# Processing_Unit.net
KiCad netlist of a schematic drawn in Altium Designer
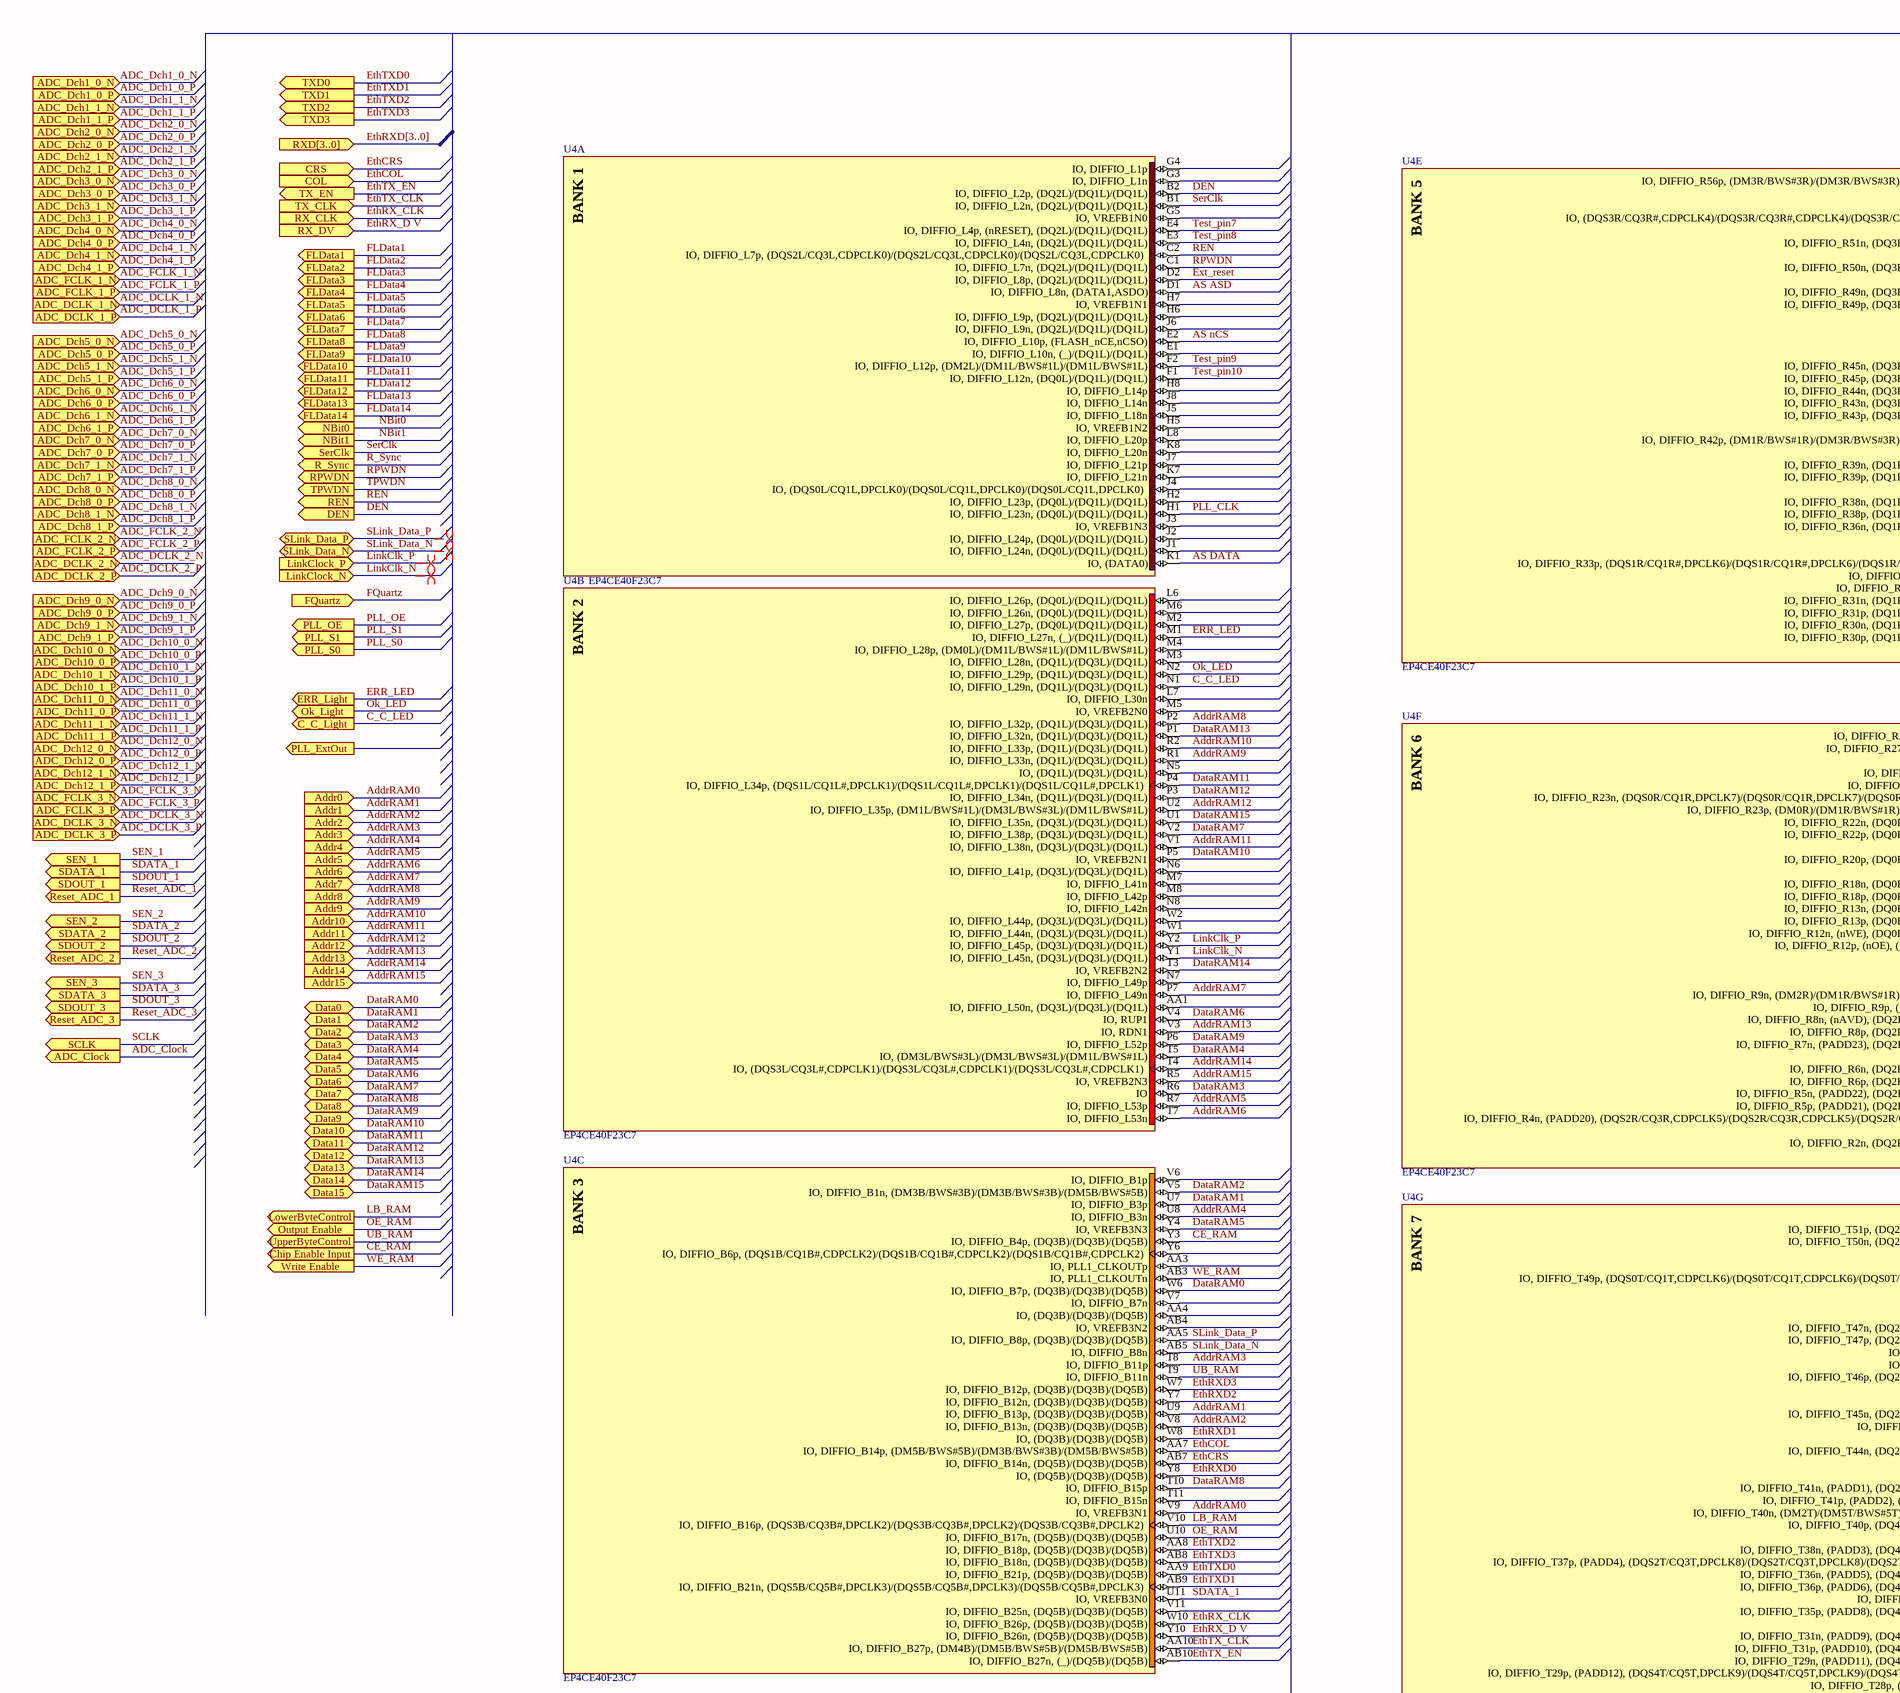
[diagram p0: Processing Unit.SchDoc, top left]
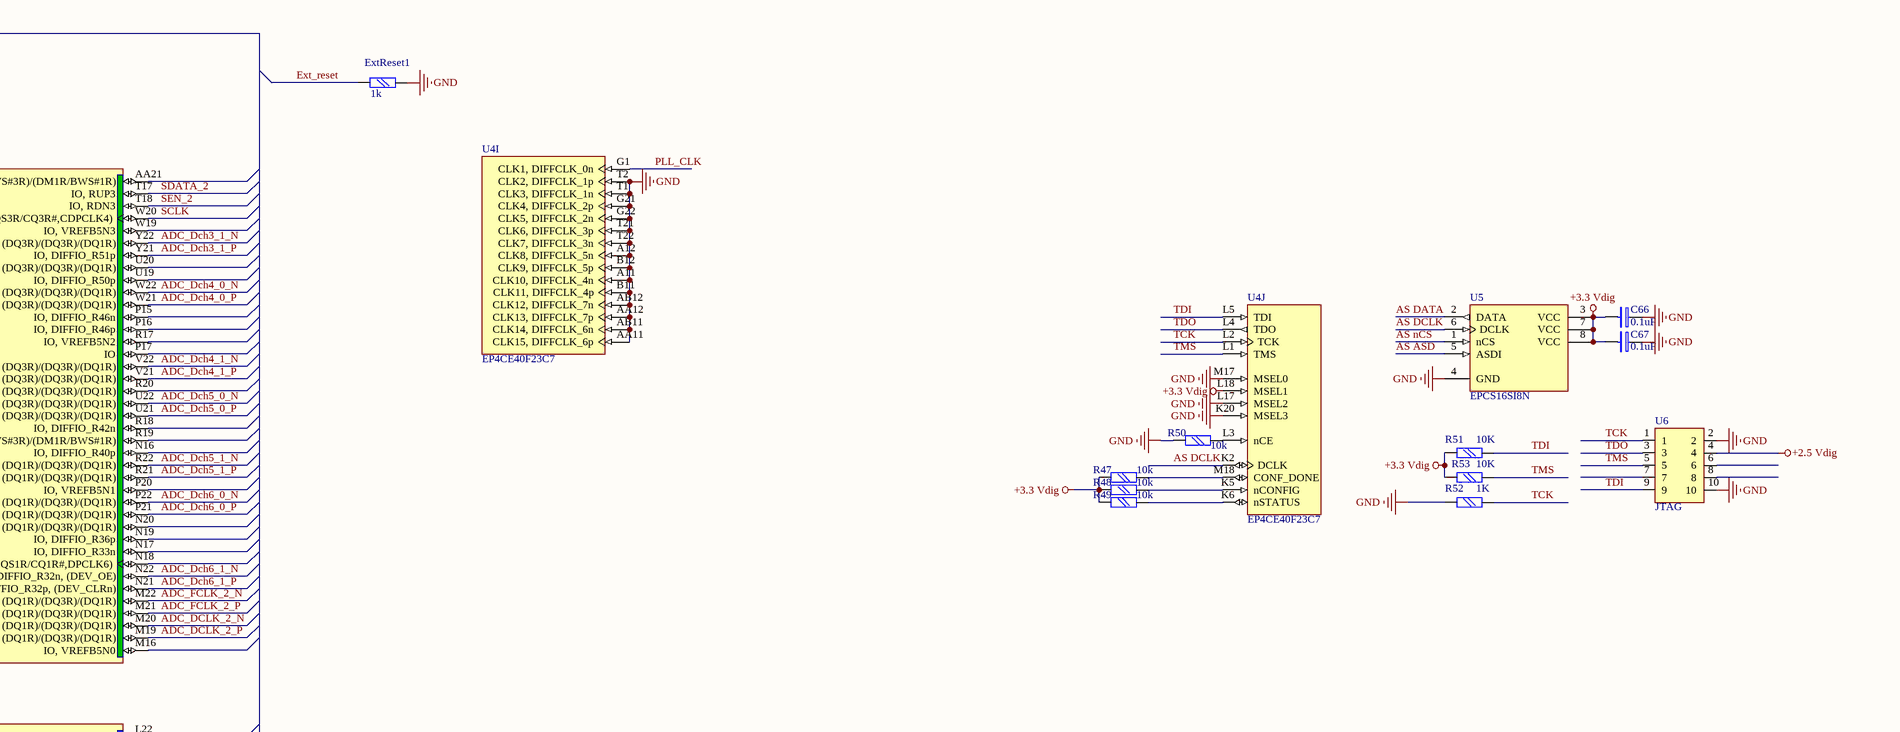
[diagram p1: Processing Unit.SchDoc, top right]
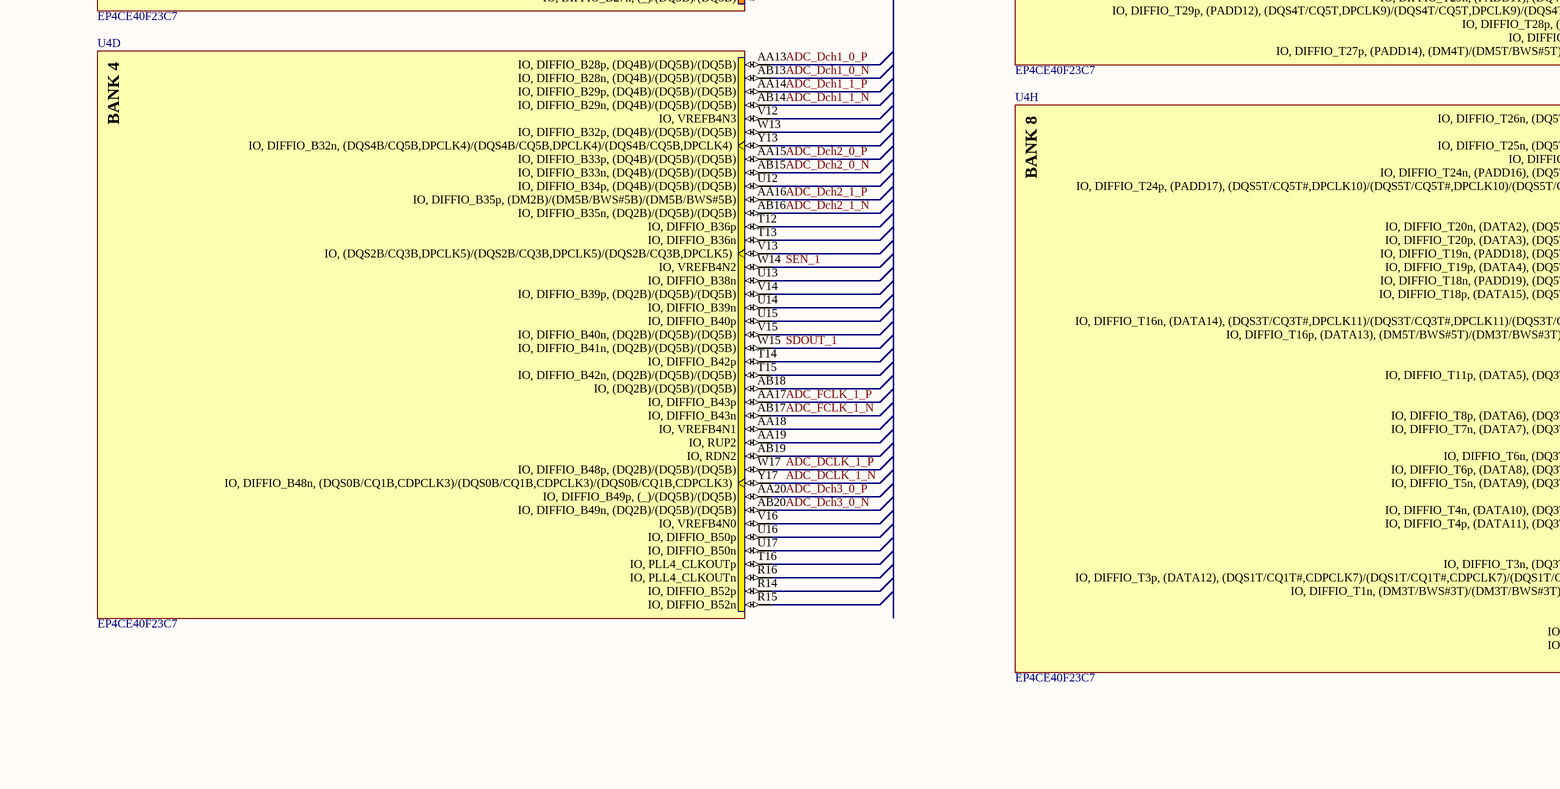
[diagram p2: Processing Unit.SchDoc, bottom left]
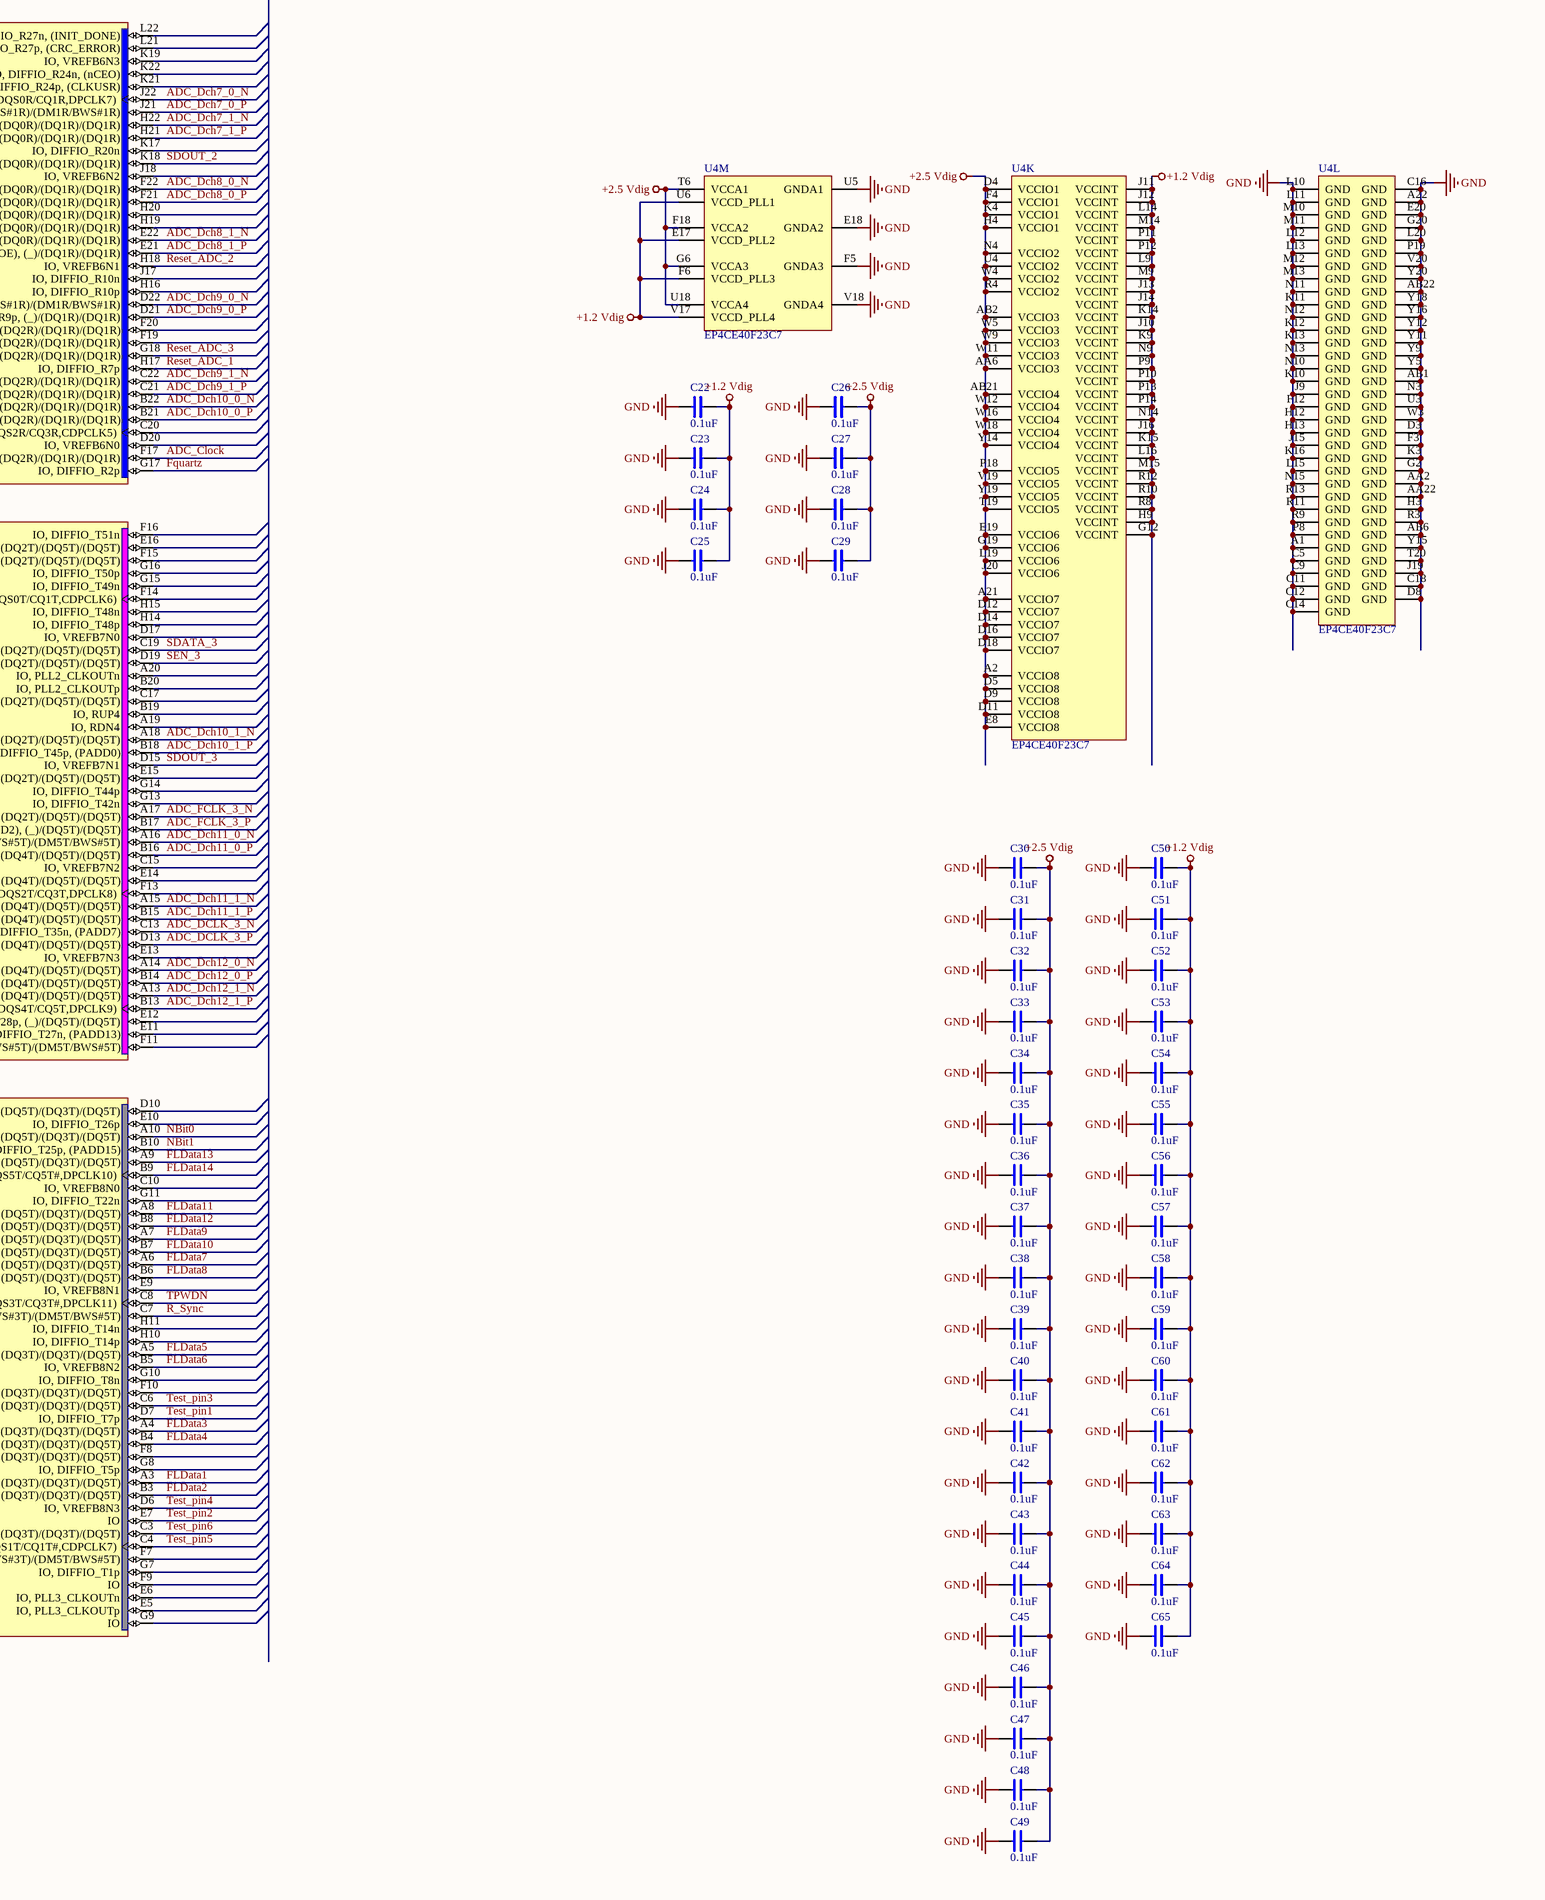
[diagram p3: Processing Unit.SchDoc, bottom right]

(export (version "E")
  (design (tool "Eeschema 10.0.6"))
  (components
    (comp (ref "C22") (value "0.1uF") (footprint "0402") (libsource (lib "*") (part "C")))
    (comp (ref "C23") (value "0.1uF") (footprint "0402") (libsource (lib "*") (part "C")))
    (comp (ref "C24") (value "0.1uF") (footprint "0402") (libsource (lib "*") (part "C")))
    (comp (ref "C25") (value "0.1uF") (footprint "0402") (libsource (lib "*") (part "C")))
    (comp (ref "C26") (value "0.1uF") (footprint "0402") (libsource (lib "*") (part "C")))
    (comp (ref "C27") (value "0.1uF") (footprint "0402") (libsource (lib "*") (part "C")))
    (comp (ref "C28") (value "0.1uF") (footprint "0402") (libsource (lib "*") (part "C")))
    (comp (ref "C29") (value "0.1uF") (footprint "0402") (libsource (lib "*") (part "C")))
    (comp (ref "C30") (value "0.1uF") (footprint "0402") (libsource (lib "*") (part "C")))
    (comp (ref "C31") (value "0.1uF") (footprint "0402") (libsource (lib "*") (part "C")))
    (comp (ref "C32") (value "0.1uF") (footprint "0402") (libsource (lib "*") (part "C")))
    (comp (ref "C33") (value "0.1uF") (footprint "0402") (libsource (lib "*") (part "C")))
    (comp (ref "C34") (value "0.1uF") (footprint "0402") (libsource (lib "*") (part "C")))
    (comp (ref "C35") (value "0.1uF") (footprint "0402") (libsource (lib "*") (part "C")))
    (comp (ref "C36") (value "0.1uF") (footprint "0402") (libsource (lib "*") (part "C")))
    (comp (ref "C37") (value "0.1uF") (footprint "0402") (libsource (lib "*") (part "C")))
    (comp (ref "C38") (value "0.1uF") (footprint "0402") (libsource (lib "*") (part "C")))
    (comp (ref "C39") (value "0.1uF") (footprint "0402") (libsource (lib "*") (part "C")))
    (comp (ref "C40") (value "0.1uF") (footprint "0402") (libsource (lib "*") (part "C")))
    (comp (ref "C41") (value "0.1uF") (footprint "0402") (libsource (lib "*") (part "C")))
    (comp (ref "C42") (value "0.1uF") (footprint "0402") (libsource (lib "*") (part "C")))
    (comp (ref "C43") (value "0.1uF") (footprint "0402") (libsource (lib "*") (part "C")))
    (comp (ref "C44") (value "0.1uF") (footprint "0402") (libsource (lib "*") (part "C")))
    (comp (ref "C45") (value "0.1uF") (footprint "0402") (libsource (lib "*") (part "C")))
    (comp (ref "C46") (value "0.1uF") (footprint "0402") (libsource (lib "*") (part "C")))
    (comp (ref "C47") (value "0.1uF") (footprint "0402") (libsource (lib "*") (part "C")))
    (comp (ref "C48") (value "0.1uF") (footprint "0402") (libsource (lib "*") (part "C")))
    (comp (ref "C49") (value "0.1uF") (footprint "0402") (libsource (lib "*") (part "C")))
    (comp (ref "C50") (value "0.1uF") (footprint "0402") (libsource (lib "*") (part "C")))
    (comp (ref "C51") (value "0.1uF") (footprint "0402") (libsource (lib "*") (part "C")))
    (comp (ref "C52") (value "0.1uF") (footprint "0402") (libsource (lib "*") (part "C")))
    (comp (ref "C53") (value "0.1uF") (footprint "0402") (libsource (lib "*") (part "C")))
    (comp (ref "C54") (value "0.1uF") (footprint "0402") (libsource (lib "*") (part "C")))
    (comp (ref "C55") (value "0.1uF") (footprint "0402") (libsource (lib "*") (part "C")))
    (comp (ref "C56") (value "0.1uF") (footprint "0402") (libsource (lib "*") (part "C")))
    (comp (ref "C57") (value "0.1uF") (footprint "0402") (libsource (lib "*") (part "C")))
    (comp (ref "C58") (value "0.1uF") (footprint "0402") (libsource (lib "*") (part "C")))
    (comp (ref "C59") (value "0.1uF") (footprint "0402") (libsource (lib "*") (part "C")))
    (comp (ref "C60") (value "0.1uF") (footprint "0402") (libsource (lib "*") (part "C")))
    (comp (ref "C61") (value "0.1uF") (footprint "0402") (libsource (lib "*") (part "C")))
    (comp (ref "C62") (value "0.1uF") (footprint "0402") (libsource (lib "*") (part "C")))
    (comp (ref "C63") (value "0.1uF") (footprint "0402") (libsource (lib "*") (part "C")))
    (comp (ref "C64") (value "0.1uF") (footprint "0402") (libsource (lib "*") (part "C")))
    (comp (ref "C65") (value "0.1uF") (footprint "0402") (libsource (lib "*") (part "C")))
    (comp (ref "C66") (value "0.1uF") (footprint "chip0603") (libsource (lib "*") (part "C")))
    (comp (ref "C67") (value "0.1uF") (footprint "chip0603") (libsource (lib "*") (part "C")))
    (comp (ref "ExtReset1") (value "1k") (footprint "chip0603") (libsource (lib "*") (part "R")))
    (comp (ref "R47") (value "10k") (footprint "chip0603") (libsource (lib "") (part "R_1")))
    (comp (ref "R48") (value "10k") (footprint "chip0603") (libsource (lib "") (part "R_1")))
    (comp (ref "R49") (value "10k") (footprint "chip0603") (libsource (lib "") (part "R_1")))
    (comp (ref "R50") (value "10k") (footprint "chip0603") (libsource (lib "") (part "R_1")))
    (comp (ref "R51") (value "10K") (footprint "chip0603") (libsource (lib "") (part "R_1")))
    (comp (ref "R52") (value "1K") (footprint "chip0603") (libsource (lib "") (part "R_1")))
    (comp (ref "R53") (value "10K") (footprint "chip0603") (libsource (lib "") (part "R_1")))
    (comp (ref "U4")
      (value "EP4CE40F23C7")
      (footprint "Altera Footprints:FBGA484")
      (fields (field (name "PUBLISHER") "Altium Limited"))
      (libsource (lib "Altera Cyclone IV E") (part "EP4CE40F23C7"))
    )
    (comp (ref "U5")
      (value "EPCS16SI8N")
      (footprint "8SO200")
      (fields (field (name "PUBLISHER") "Altium Limited"))
      (libsource (lib "Altera EPCS Configuration Device") (part "EPCS4SI8N"))
    )
    (comp (ref "U6") (value "JTAG") (footprint "IDC10") (libsource (lib "vDevice") (part "IDC-10")))
  )
  (nets
    (net (code "1") (name "+1.2 Vdig") (class "Default")
      (node (ref "C22") (pin "2") (pinfunction "2_2") (pintype "passive"))
      (node (ref "C23") (pin "2") (pinfunction "2_2") (pintype "passive"))
      (node (ref "C24") (pin "2") (pinfunction "2_2") (pintype "passive"))
      (node (ref "C25") (pin "2") (pinfunction "2_2") (pintype "passive"))
      (node (ref "C50") (pin "2") (pinfunction "2_2") (pintype "passive"))
      (node (ref "C51") (pin "2") (pinfunction "2_2") (pintype "passive"))
      (node (ref "C52") (pin "2") (pinfunction "2_2") (pintype "passive"))
      (node (ref "C53") (pin "2") (pinfunction "2_2") (pintype "passive"))
      (node (ref "C54") (pin "2") (pinfunction "2_2") (pintype "passive"))
      (node (ref "C55") (pin "2") (pinfunction "2_2") (pintype "passive"))
      (node (ref "C56") (pin "2") (pinfunction "2_2") (pintype "passive"))
      (node (ref "C57") (pin "2") (pinfunction "2_2") (pintype "passive"))
      (node (ref "C58") (pin "2") (pinfunction "2_2") (pintype "passive"))
      (node (ref "C59") (pin "2") (pinfunction "2_2") (pintype "passive"))
      (node (ref "C60") (pin "2") (pinfunction "2_2") (pintype "passive"))
      (node (ref "C61") (pin "2") (pinfunction "2_2") (pintype "passive"))
      (node (ref "C62") (pin "2") (pinfunction "2_2") (pintype "passive"))
      (node (ref "C63") (pin "2") (pinfunction "2_2") (pintype "passive"))
      (node (ref "C64") (pin "2") (pinfunction "2_2") (pintype "passive"))
      (node (ref "C65") (pin "2") (pinfunction "2_2") (pintype "passive"))
      (node (ref "U4") (pin "E17") (pinfunction "VCCD_PLL2_E17") (pintype "power_in"))
      (node (ref "U4") (pin "F6") (pinfunction "VCCD_PLL3_F6") (pintype "power_in"))
      (node (ref "U4") (pin "G12") (pinfunction "VCCINT_G12") (pintype "power_in"))
      (node (ref "U4") (pin "H9") (pinfunction "VCCINT_H9") (pintype "power_in"))
      (node (ref "U4") (pin "J10") (pinfunction "VCCINT_J10") (pintype "power_in"))
      (node (ref "U4") (pin "J11") (pinfunction "VCCINT_J11") (pintype "power_in"))
      (node (ref "U4") (pin "J12") (pinfunction "VCCINT_J12") (pintype "power_in"))
      (node (ref "U4") (pin "J13") (pinfunction "VCCINT_J13") (pintype "power_in"))
      (node (ref "U4") (pin "J14") (pinfunction "VCCINT_J14") (pintype "power_in"))
      (node (ref "U4") (pin "J16") (pinfunction "VCCINT_J16") (pintype "power_in"))
      (node (ref "U4") (pin "K14") (pinfunction "VCCINT_K14") (pintype "power_in"))
      (node (ref "U4") (pin "K15") (pinfunction "VCCINT_K15") (pintype "power_in"))
      (node (ref "U4") (pin "K9") (pinfunction "VCCINT_K9") (pintype "power_in"))
      (node (ref "U4") (pin "L14") (pinfunction "VCCINT_L14") (pintype "power_in"))
      (node (ref "U4") (pin "L16") (pinfunction "VCCINT_L16") (pintype "power_in"))
      (node (ref "U4") (pin "L9") (pinfunction "VCCINT_L9") (pintype "power_in"))
      (node (ref "U4") (pin "M14") (pinfunction "VCCINT_M14") (pintype "power_in"))
      (node (ref "U4") (pin "M15") (pinfunction "VCCINT_M15") (pintype "power_in"))
      (node (ref "U4") (pin "M9") (pinfunction "VCCINT_M9") (pintype "power_in"))
      (node (ref "U4") (pin "N14") (pinfunction "VCCINT_N14") (pintype "power_in"))
      (node (ref "U4") (pin "N9") (pinfunction "VCCINT_N9") (pintype "power_in"))
      (node (ref "U4") (pin "P10") (pinfunction "VCCINT_P10") (pintype "power_in"))
      (node (ref "U4") (pin "P11") (pinfunction "VCCINT_P11") (pintype "power_in"))
      (node (ref "U4") (pin "P12") (pinfunction "VCCINT_P12") (pintype "power_in"))
      (node (ref "U4") (pin "P13") (pinfunction "VCCINT_P13") (pintype "power_in"))
      (node (ref "U4") (pin "P14") (pinfunction "VCCINT_P14") (pintype "power_in"))
      (node (ref "U4") (pin "P9") (pinfunction "VCCINT_P9") (pintype "power_in"))
      (node (ref "U4") (pin "R10") (pinfunction "VCCINT_R10") (pintype "power_in"))
      (node (ref "U4") (pin "R12") (pinfunction "VCCINT_R12") (pintype "power_in"))
      (node (ref "U4") (pin "R8") (pinfunction "VCCINT_R8") (pintype "power_in"))
      (node (ref "U4") (pin "U6") (pinfunction "VCCD_PLL1_U6") (pintype "power_in"))
      (node (ref "U4") (pin "V17") (pinfunction "VCCD_PLL4_V17") (pintype "power_in"))
    )
    (net (code "2") (name "+2.5 Vdig") (class "Default")
      (node (ref "C26") (pin "2") (pinfunction "2_2") (pintype "passive"))
      (node (ref "C27") (pin "2") (pinfunction "2_2") (pintype "passive"))
      (node (ref "C28") (pin "2") (pinfunction "2_2") (pintype "passive"))
      (node (ref "C29") (pin "2") (pinfunction "2_2") (pintype "passive"))
      (node (ref "C30") (pin "2") (pinfunction "2_2") (pintype "passive"))
      (node (ref "C31") (pin "2") (pinfunction "2_2") (pintype "passive"))
      (node (ref "C32") (pin "2") (pinfunction "2_2") (pintype "passive"))
      (node (ref "C33") (pin "2") (pinfunction "2_2") (pintype "passive"))
      (node (ref "C34") (pin "2") (pinfunction "2_2") (pintype "passive"))
      (node (ref "C35") (pin "2") (pinfunction "2_2") (pintype "passive"))
      (node (ref "C36") (pin "2") (pinfunction "2_2") (pintype "passive"))
      (node (ref "C37") (pin "2") (pinfunction "2_2") (pintype "passive"))
      (node (ref "C38") (pin "2") (pinfunction "2_2") (pintype "passive"))
      (node (ref "C39") (pin "2") (pinfunction "2_2") (pintype "passive"))
      (node (ref "C40") (pin "2") (pinfunction "2_2") (pintype "passive"))
      (node (ref "C41") (pin "2") (pinfunction "2_2") (pintype "passive"))
      (node (ref "C42") (pin "2") (pinfunction "2_2") (pintype "passive"))
      (node (ref "C43") (pin "2") (pinfunction "2_2") (pintype "passive"))
      (node (ref "C44") (pin "2") (pinfunction "2_2") (pintype "passive"))
      (node (ref "C45") (pin "2") (pinfunction "2_2") (pintype "passive"))
      (node (ref "C46") (pin "2") (pinfunction "2_2") (pintype "passive"))
      (node (ref "C47") (pin "2") (pinfunction "2_2") (pintype "passive"))
      (node (ref "C48") (pin "2") (pinfunction "2_2") (pintype "passive"))
      (node (ref "C49") (pin "2") (pinfunction "2_2") (pintype "passive"))
      (node (ref "U4") (pin "A2") (pinfunction "VCCIO8_A2") (pintype "power_in"))
      (node (ref "U4") (pin "A21") (pinfunction "VCCIO7_A21") (pintype "power_in"))
      (node (ref "U4") (pin "AA6") (pinfunction "VCCIO3_AA6") (pintype "power_in"))
      (node (ref "U4") (pin "AB2") (pinfunction "VCCIO3_AB2") (pintype "power_in"))
      (node (ref "U4") (pin "AB21") (pinfunction "VCCIO4_AB21") (pintype "power_in"))
      (node (ref "U4") (pin "D11") (pinfunction "VCCIO8_D11") (pintype "power_in"))
      (node (ref "U4") (pin "D12") (pinfunction "VCCIO7_D12") (pintype "power_in"))
      (node (ref "U4") (pin "D14") (pinfunction "VCCIO7_D14") (pintype "power_in"))
      (node (ref "U4") (pin "D16") (pinfunction "VCCIO7_D16") (pintype "power_in"))
      (node (ref "U4") (pin "D18") (pinfunction "VCCIO7_D18") (pintype "power_in"))
      (node (ref "U4") (pin "D4") (pinfunction "VCCIO1_D4") (pintype "power_in"))
      (node (ref "U4") (pin "D5") (pinfunction "VCCIO8_D5") (pintype "power_in"))
      (node (ref "U4") (pin "D9") (pinfunction "VCCIO8_D9") (pintype "power_in"))
      (node (ref "U4") (pin "E19") (pinfunction "VCCIO6_E19") (pintype "power_in"))
      (node (ref "U4") (pin "E8") (pinfunction "VCCIO8_E8") (pintype "power_in"))
      (node (ref "U4") (pin "F18") (pinfunction "VCCA2_F18") (pintype "power_in"))
      (node (ref "U4") (pin "F4") (pinfunction "VCCIO1_F4") (pintype "power_in"))
      (node (ref "U4") (pin "G19") (pinfunction "VCCIO6_G19") (pintype "power_in"))
      (node (ref "U4") (pin "G6") (pinfunction "VCCA3_G6") (pintype "power_in"))
      (node (ref "U4") (pin "H4") (pinfunction "VCCIO1_H4") (pintype "power_in"))
      (node (ref "U4") (pin "J20") (pinfunction "VCCIO6_J20") (pintype "power_in"))
      (node (ref "U4") (pin "K4") (pinfunction "VCCIO1_K4") (pintype "power_in"))
      (node (ref "U4") (pin "L19") (pinfunction "VCCIO6_L19") (pintype "power_in"))
      (node (ref "U4") (pin "N4") (pinfunction "VCCIO2_N4") (pintype "power_in"))
      (node (ref "U4") (pin "P18") (pinfunction "VCCIO5_P18") (pintype "power_in"))
      (node (ref "U4") (pin "R4") (pinfunction "VCCIO2_R4") (pintype "power_in"))
      (node (ref "U4") (pin "T19") (pinfunction "VCCIO5_T19") (pintype "power_in"))
      (node (ref "U4") (pin "T6") (pinfunction "VCCA1_T6") (pintype "power_in"))
      (node (ref "U4") (pin "U18") (pinfunction "VCCA4_U18") (pintype "power_in"))
      (node (ref "U4") (pin "U4") (pinfunction "VCCIO2_U4") (pintype "power_in"))
      (node (ref "U4") (pin "V19") (pinfunction "VCCIO5_V19") (pintype "power_in"))
      (node (ref "U4") (pin "W11") (pinfunction "VCCIO3_W11") (pintype "power_in"))
      (node (ref "U4") (pin "W12") (pinfunction "VCCIO4_W12") (pintype "power_in"))
      (node (ref "U4") (pin "W16") (pinfunction "VCCIO4_W16") (pintype "power_in"))
      (node (ref "U4") (pin "W18") (pinfunction "VCCIO4_W18") (pintype "power_in"))
      (node (ref "U4") (pin "W4") (pinfunction "VCCIO2_W4") (pintype "power_in"))
      (node (ref "U4") (pin "W5") (pinfunction "VCCIO3_W5") (pintype "power_in"))
      (node (ref "U4") (pin "W9") (pinfunction "VCCIO3_W9") (pintype "power_in"))
      (node (ref "U4") (pin "Y14") (pinfunction "VCCIO4_Y14") (pintype "power_in"))
      (node (ref "U4") (pin "Y19") (pinfunction "VCCIO5_Y19") (pintype "power_in"))
      (node (ref "U6") (pin "4") (pinfunction "4_4") (pintype "bidirectional"))
    )
    (net (code "3") (name "+3.3 Vdig") (class "Default")
      (node (ref "C66") (pin "2") (pinfunction "2_2") (pintype "passive"))
      (node (ref "C67") (pin "2") (pinfunction "2_2") (pintype "passive"))
      (node (ref "R47") (pin "1") (pinfunction "1_1") (pintype "passive"))
      (node (ref "R48") (pin "1") (pinfunction "1_1") (pintype "passive"))
      (node (ref "R49") (pin "1") (pinfunction "1_1") (pintype "passive"))
      (node (ref "R51") (pin "1") (pinfunction "1_1") (pintype "passive"))
      (node (ref "R53") (pin "1") (pinfunction "1_1") (pintype "passive"))
      (node (ref "U4") (pin "L18") (pinfunction "MSEL1_L18") (pintype "input"))
      (node (ref "U5") (pin "3") (pinfunction "VCC_3") (pintype "power_in"))
      (node (ref "U5") (pin "7") (pinfunction "VCC_7") (pintype "power_in"))
      (node (ref "U5") (pin "8") (pinfunction "VCC_8") (pintype "power_in"))
    )
    (net (code "4") (name "/ADC_Clock") (class "Default")
      (node (ref "U4") (pin "F17") (pinfunction "IO,_DIFFIO_R2n,_(DQ2R)/(DQ1R)/(DQ1R)_F17") (pintype "bidirectional"))
    )
    (net (code "5") (name "/ADC_DCLK_1_N") (class "Default")
      (node (ref "U4") (pin "Y17") (pinfunction "IO,_DIFFIO_B48n,_(DQS0B/CQ1B,CDPCLK3)/(DQS0B/CQ1B,CDPCLK3)/(DQS0B/CQ1B,CDPCLK3)_Y17") (pintype "bidirectional"))
    )
    (net (code "6") (name "/ADC_DCLK_1_P") (class "Default")
      (node (ref "U4") (pin "W17") (pinfunction "IO,_DIFFIO_B48p,_(DQ2B)/(DQ5B)/(DQ5B)_W17") (pintype "bidirectional"))
    )
    (net (code "7") (name "/ADC_DCLK_2_N") (class "Default")
      (node (ref "U4") (pin "M20") (pinfunction "IO,_DIFFIO_R30n,_(DQ1R)/(DQ3R)/(DQ1R)_M20") (pintype "bidirectional"))
    )
    (net (code "8") (name "/ADC_DCLK_2_P") (class "Default")
      (node (ref "U4") (pin "M19") (pinfunction "IO,_DIFFIO_R30p,_(DQ1R)/(DQ3R)/(DQ1R)_M19") (pintype "bidirectional"))
    )
    (net (code "9") (name "/ADC_DCLK_3_N") (class "Default")
      (node (ref "U4") (pin "C13") (pinfunction "IO,_DIFFIO_T35n,_(PADD7)_C13") (pintype "bidirectional"))
    )
    (net (code "10") (name "/ADC_DCLK_3_P") (class "Default")
      (node (ref "U4") (pin "D13") (pinfunction "IO,_DIFFIO_T35p,_(PADD8),_(DQ4T)/(DQ5T)/(DQ5T)_D13") (pintype "bidirectional"))
    )
    (net (code "11") (name "/ADC_Dch1_0_N") (class "Default")
      (node (ref "U4") (pin "AB13") (pinfunction "IO,_DIFFIO_B28n,_(DQ4B)/(DQ5B)/(DQ5B)_AB13") (pintype "bidirectional"))
    )
    (net (code "12") (name "/ADC_Dch1_0_P") (class "Default")
      (node (ref "U4") (pin "AA13") (pinfunction "IO,_DIFFIO_B28p,_(DQ4B)/(DQ5B)/(DQ5B)_AA13") (pintype "bidirectional"))
    )
    (net (code "13") (name "/ADC_Dch1_1_N") (class "Default")
      (node (ref "U4") (pin "AB14") (pinfunction "IO,_DIFFIO_B29n,_(DQ4B)/(DQ5B)/(DQ5B)_AB14") (pintype "bidirectional"))
    )
    (net (code "14") (name "/ADC_Dch1_1_P") (class "Default")
      (node (ref "U4") (pin "AA14") (pinfunction "IO,_DIFFIO_B29p,_(DQ4B)/(DQ5B)/(DQ5B)_AA14") (pintype "bidirectional"))
    )
    (net (code "15") (name "/ADC_Dch2_0_N") (class "Default")
      (node (ref "U4") (pin "AB15") (pinfunction "IO,_DIFFIO_B33n,_(DQ4B)/(DQ5B)/(DQ5B)_AB15") (pintype "bidirectional"))
    )
    (net (code "16") (name "/ADC_Dch2_0_P") (class "Default")
      (node (ref "U4") (pin "AA15") (pinfunction "IO,_DIFFIO_B33p,_(DQ4B)/(DQ5B)/(DQ5B)_AA15") (pintype "bidirectional"))
    )
    (net (code "17") (name "/ADC_Dch2_1_N") (class "Default")
      (node (ref "U4") (pin "AB16") (pinfunction "IO,_DIFFIO_B35n,_(DQ2B)/(DQ5B)/(DQ5B)_AB16") (pintype "bidirectional"))
    )
    (net (code "18") (name "/ADC_Dch2_1_P") (class "Default")
      (node (ref "U4") (pin "AA16") (pinfunction "IO,_DIFFIO_B35p,_(DM2B)/(DM5B/BWS#5B)/(DM5B/BWS#5B)_AA16") (pintype "bidirectional"))
    )
    (net (code "19") (name "/ADC_Dch3_0_N") (class "Default")
      (node (ref "U4") (pin "AB20") (pinfunction "IO,_DIFFIO_B49n,_(DQ2B)/(DQ5B)/(DQ5B)_AB20") (pintype "bidirectional"))
    )
    (net (code "20") (name "/ADC_Dch3_0_P") (class "Default")
      (node (ref "U4") (pin "AA20") (pinfunction "IO,_DIFFIO_B49p,_(_)/(DQ5B)/(DQ5B)_AA20") (pintype "bidirectional"))
    )
    (net (code "21") (name "/ADC_Dch3_1_N") (class "Default")
      (node (ref "U4") (pin "Y22") (pinfunction "IO,_DIFFIO_R51n,_(DQ3R)/(DQ3R)/(DQ1R)_Y22") (pintype "bidirectional"))
    )
    (net (code "22") (name "/ADC_Dch3_1_P") (class "Default")
      (node (ref "U4") (pin "Y21") (pinfunction "IO,_DIFFIO_R51p_Y21") (pintype "bidirectional"))
    )
    (net (code "23") (name "/ADC_Dch4_0_N") (class "Default")
      (node (ref "U4") (pin "W22") (pinfunction "IO,_DIFFIO_R49n,_(DQ3R)/(DQ3R)/(DQ1R)_W22") (pintype "bidirectional"))
    )
    (net (code "24") (name "/ADC_Dch4_0_P") (class "Default")
      (node (ref "U4") (pin "W21") (pinfunction "IO,_DIFFIO_R49p,_(DQ3R)/(DQ3R)/(DQ1R)_W21") (pintype "bidirectional"))
    )
    (net (code "25") (name "/ADC_Dch4_1_N") (class "Default")
      (node (ref "U4") (pin "V22") (pinfunction "IO,_DIFFIO_R45n,_(DQ3R)/(DQ3R)/(DQ1R)_V22") (pintype "bidirectional"))
    )
    (net (code "26") (name "/ADC_Dch4_1_P") (class "Default")
      (node (ref "U4") (pin "V21") (pinfunction "IO,_DIFFIO_R45p,_(DQ3R)/(DQ3R)/(DQ1R)_V21") (pintype "bidirectional"))
    )
    (net (code "27") (name "/ADC_Dch5_0_N") (class "Default")
      (node (ref "U4") (pin "U22") (pinfunction "IO,_DIFFIO_R43n,_(DQ3R)/(DQ3R)/(DQ1R)_U22") (pintype "bidirectional"))
    )
    (net (code "28") (name "/ADC_Dch5_0_P") (class "Default")
      (node (ref "U4") (pin "U21") (pinfunction "IO,_DIFFIO_R43p,_(DQ3R)/(DQ3R)/(DQ1R)_U21") (pintype "bidirectional"))
    )
    (net (code "29") (name "/ADC_Dch5_1_N") (class "Default")
      (node (ref "U4") (pin "R22") (pinfunction "IO,_DIFFIO_R39n,_(DQ1R)/(DQ3R)/(DQ1R)_R22") (pintype "bidirectional"))
    )
    (net (code "30") (name "/ADC_Dch5_1_P") (class "Default")
      (node (ref "U4") (pin "R21") (pinfunction "IO,_DIFFIO_R39p,_(DQ1R)/(DQ3R)/(DQ1R)_R21") (pintype "bidirectional"))
    )
    (net (code "31") (name "/ADC_Dch6_0_N") (class "Default")
      (node (ref "U4") (pin "P22") (pinfunction "IO,_DIFFIO_R38n,_(DQ1R)/(DQ3R)/(DQ1R)_P22") (pintype "bidirectional"))
    )
    (net (code "32") (name "/ADC_Dch6_0_P") (class "Default")
      (node (ref "U4") (pin "P21") (pinfunction "IO,_DIFFIO_R38p,_(DQ1R)/(DQ3R)/(DQ1R)_P21") (pintype "bidirectional"))
    )
    (net (code "33") (name "/ADC_Dch6_1_N") (class "Default")
      (node (ref "U4") (pin "N22") (pinfunction "IO,_DIFFIO_R32n,_(DEV_OE)_N22") (pintype "bidirectional"))
    )
    (net (code "34") (name "/ADC_Dch6_1_P") (class "Default")
      (node (ref "U4") (pin "N21") (pinfunction "IO,_DIFFIO_R32p,_(DEV_CLRn)_N21") (pintype "bidirectional"))
    )
    (net (code "35") (name "/ADC_Dch7_0_N") (class "Default")
      (node (ref "U4") (pin "J22") (pinfunction "IO,_DIFFIO_R23n,_(DQS0R/CQ1R,DPCLK7)/(DQS0R/CQ1R,DPCLK7)/(DQS0R/CQ1R,DPCLK7)_J22") (pintype "bidirectional"))
    )
    (net (code "36") (name "/ADC_Dch7_0_P") (class "Default")
      (node (ref "U4") (pin "J21") (pinfunction "IO,_DIFFIO_R23p,_(DM0R)/(DM1R/BWS#1R)/(DM1R/BWS#1R)_J21") (pintype "bidirectional"))
    )
    (net (code "37") (name "/ADC_Dch7_1_N") (class "Default")
      (node (ref "U4") (pin "H22") (pinfunction "IO,_DIFFIO_R22n,_(DQ0R)/(DQ1R)/(DQ1R)_H22") (pintype "bidirectional"))
    )
    (net (code "38") (name "/ADC_Dch7_1_P") (class "Default")
      (node (ref "U4") (pin "H21") (pinfunction "IO,_DIFFIO_R22p,_(DQ0R)/(DQ1R)/(DQ1R)_H21") (pintype "bidirectional"))
    )
    (net (code "39") (name "/ADC_Dch8_0_N") (class "Default")
      (node (ref "U4") (pin "F22") (pinfunction "IO,_DIFFIO_R18n,_(DQ0R)/(DQ1R)/(DQ1R)_F22") (pintype "bidirectional"))
    )
    (net (code "40") (name "/ADC_Dch8_0_P") (class "Default")
      (node (ref "U4") (pin "F21") (pinfunction "IO,_DIFFIO_R18p,_(DQ0R)/(DQ1R)/(DQ1R)_F21") (pintype "bidirectional"))
    )
    (net (code "41") (name "/ADC_Dch8_1_N") (class "Default")
      (node (ref "U4") (pin "E22") (pinfunction "IO,_DIFFIO_R12n,_(nWE),_(DQ0R)/(DQ1R)/(DQ1R)_E22") (pintype "bidirectional"))
    )
    (net (code "42") (name "/ADC_Dch8_1_P") (class "Default")
      (node (ref "U4") (pin "E21") (pinfunction "IO,_DIFFIO_R12p,_(nOE),_(_)/(DQ1R)/(DQ1R)_E21") (pintype "bidirectional"))
    )
    (net (code "43") (name "/ADC_Dch9_0_N") (class "Default")
      (node (ref "U4") (pin "D22") (pinfunction "IO,_DIFFIO_R9n,_(DM2R)/(DM1R/BWS#1R)/(DM1R/BWS#1R)_D22") (pintype "bidirectional"))
    )
    (net (code "44") (name "/ADC_Dch9_0_P") (class "Default")
      (node (ref "U4") (pin "D21") (pinfunction "IO,_DIFFIO_R9p,_(_)/(DQ1R)/(DQ1R)_D21") (pintype "bidirectional"))
    )
    (net (code "45") (name "/ADC_Dch9_1_N") (class "Default")
      (node (ref "U4") (pin "C22") (pinfunction "IO,_DIFFIO_R6n,_(DQ2R)/(DQ1R)/(DQ1R)_C22") (pintype "bidirectional"))
    )
    (net (code "46") (name "/ADC_Dch9_1_P") (class "Default")
      (node (ref "U4") (pin "C21") (pinfunction "IO,_DIFFIO_R6p,_(DQ2R)/(DQ1R)/(DQ1R)_C21") (pintype "bidirectional"))
    )
    (net (code "47") (name "/ADC_Dch10_0_N") (class "Default")
      (node (ref "U4") (pin "B22") (pinfunction "IO,_DIFFIO_R5n,_(PADD22),_(DQ2R)/(DQ1R)/(DQ1R)_B22") (pintype "bidirectional"))
    )
    (net (code "48") (name "/ADC_Dch10_0_P") (class "Default")
      (node (ref "U4") (pin "B21") (pinfunction "IO,_DIFFIO_R5p,_(PADD21),_(DQ2R)/(DQ1R)/(DQ1R)_B21") (pintype "bidirectional"))
    )
    (net (code "49") (name "/ADC_Dch10_1_N") (class "Default")
      (node (ref "U4") (pin "A18") (pinfunction "IO,_DIFFIO_T45n,_(DQ2T)/(DQ5T)/(DQ5T)_A18") (pintype "bidirectional"))
    )
    (net (code "50") (name "/ADC_Dch10_1_P") (class "Default")
      (node (ref "U4") (pin "B18") (pinfunction "IO,_DIFFIO_T45p,_(PADD0)_B18") (pintype "bidirectional"))
    )
    (net (code "51") (name "/ADC_Dch11_0_N") (class "Default")
      (node (ref "U4") (pin "A16") (pinfunction "IO,_DIFFIO_T40n,_(DM2T)/(DM5T/BWS#5T)/(DM5T/BWS#5T)_A16") (pintype "bidirectional"))
    )
    (net (code "52") (name "/ADC_Dch11_0_P") (class "Default")
      (node (ref "U4") (pin "B16") (pinfunction "IO,_DIFFIO_T40p,_(DQ4T)/(DQ5T)/(DQ5T)_B16") (pintype "bidirectional"))
    )
    (net (code "53") (name "/ADC_Dch11_1_N") (class "Default")
      (node (ref "U4") (pin "A15") (pinfunction "IO,_DIFFIO_T36n,_(PADD5),_(DQ4T)/(DQ5T)/(DQ5T)_A15") (pintype "bidirectional"))
    )
    (net (code "54") (name "/ADC_Dch11_1_P") (class "Default")
      (node (ref "U4") (pin "B15") (pinfunction "IO,_DIFFIO_T36p,_(PADD6),_(DQ4T)/(DQ5T)/(DQ5T)_B15") (pintype "bidirectional"))
    )
    (net (code "55") (name "/ADC_Dch12_0_N") (class "Default")
      (node (ref "U4") (pin "A14") (pinfunction "IO,_DIFFIO_T31n,_(PADD9),_(DQ4T)/(DQ5T)/(DQ5T)_A14") (pintype "bidirectional"))
    )
    (net (code "56") (name "/ADC_Dch12_0_P") (class "Default")
      (node (ref "U4") (pin "B14") (pinfunction "IO,_DIFFIO_T31p,_(PADD10),_(DQ4T)/(DQ5T)/(DQ5T)_B14") (pintype "bidirectional"))
    )
    (net (code "57") (name "/ADC_Dch12_1_N") (class "Default")
      (node (ref "U4") (pin "A13") (pinfunction "IO,_DIFFIO_T29n,_(PADD11),_(DQ4T)/(DQ5T)/(DQ5T)_A13") (pintype "bidirectional"))
    )
    (net (code "58") (name "/ADC_Dch12_1_P") (class "Default")
      (node (ref "U4") (pin "B13") (pinfunction "IO,_DIFFIO_T29p,_(PADD12),_(DQS4T/CQ5T,DPCLK9)/(DQS4T/CQ5T,DPCLK9)/(DQS4T/CQ5T,DPCLK9)_B13") (pintype "bidirectional"))
    )
    (net (code "59") (name "/ADC_FCLK_1_N") (class "Default")
      (node (ref "U4") (pin "AB17") (pinfunction "IO,_DIFFIO_B43n_AB17") (pintype "bidirectional"))
    )
    (net (code "60") (name "/ADC_FCLK_1_P") (class "Default")
      (node (ref "U4") (pin "AA17") (pinfunction "IO,_DIFFIO_B43p_AA17") (pintype "bidirectional"))
    )
    (net (code "61") (name "/ADC_FCLK_2_N") (class "Default")
      (node (ref "U4") (pin "M22") (pinfunction "IO,_DIFFIO_R31n,_(DQ1R)/(DQ3R)/(DQ1R)_M22") (pintype "bidirectional"))
    )
    (net (code "62") (name "/ADC_FCLK_2_P") (class "Default")
      (node (ref "U4") (pin "M21") (pinfunction "IO,_DIFFIO_R31p,_(DQ1R)/(DQ3R)/(DQ1R)_M21") (pintype "bidirectional"))
    )
    (net (code "63") (name "/ADC_FCLK_3_N") (class "Default")
      (node (ref "U4") (pin "A17") (pinfunction "IO,_DIFFIO_T41n,_(PADD1),_(DQ2T)/(DQ5T)/(DQ5T)_A17") (pintype "bidirectional"))
    )
    (net (code "64") (name "/ADC_FCLK_3_P") (class "Default")
      (node (ref "U4") (pin "B17") (pinfunction "IO,_DIFFIO_T41p,_(PADD2),_(_)/(DQ5T)/(DQ5T)_B17") (pintype "bidirectional"))
    )
    (net (code "65") (name "/AS ASD") (class "Default")
      (node (ref "U4") (pin "D1") (pinfunction "IO,_DIFFIO_L8n,_(DATA1,ASDO)_D1") (pintype "bidirectional"))
      (node (ref "U5") (pin "5") (pinfunction "ASDI_5") (pintype "input"))
    )
    (net (code "66") (name "/AS DATA") (class "Default")
      (node (ref "U4") (pin "K1") (pinfunction "IO,_(DATA0)_K1") (pintype "bidirectional"))
      (node (ref "U5") (pin "2") (pinfunction "DATA_2") (pintype "output"))
    )
    (net (code "67") (name "/AS DCLK") (class "Default")
      (node (ref "U4") (pin "K2") (pinfunction "DCLK_K2") (pintype "bidirectional"))
      (node (ref "U5") (pin "6") (pinfunction "DCLK_6") (pintype "input"))
    )
    (net (code "68") (name "/AS nCS") (class "Default")
      (node (ref "U4") (pin "E2") (pinfunction "IO,_DIFFIO_L10p,_(FLASH_nCE,nCSO)_E2") (pintype "bidirectional"))
      (node (ref "U5") (pin "1") (pinfunction "nCS_1") (pintype "input"))
    )
    (net (code "69") (name "/AddrRAM0") (class "Default")
      (node (ref "U4") (pin "V9") (pinfunction "IO,_VREFB3N1_V9") (pintype "bidirectional"))
    )
    (net (code "70") (name "/AddrRAM1") (class "Default")
      (node (ref "U4") (pin "U9") (pinfunction "IO,_DIFFIO_B13p,_(DQ3B)/(DQ3B)/(DQ5B)_U9") (pintype "bidirectional"))
    )
    (net (code "71") (name "/AddrRAM2") (class "Default")
      (node (ref "U4") (pin "V8") (pinfunction "IO,_DIFFIO_B13n,_(DQ3B)/(DQ3B)/(DQ5B)_V8") (pintype "bidirectional"))
    )
    (net (code "72") (name "/AddrRAM3") (class "Default")
      (node (ref "U4") (pin "T8") (pinfunction "IO,_DIFFIO_B11p_T8") (pintype "bidirectional"))
    )
    (net (code "73") (name "/AddrRAM4") (class "Default")
      (node (ref "U4") (pin "U8") (pinfunction "IO,_DIFFIO_B3n_U8") (pintype "bidirectional"))
    )
    (net (code "74") (name "/AddrRAM5") (class "Default")
      (node (ref "U4") (pin "R7") (pinfunction "IO,_DIFFIO_L53p_R7") (pintype "bidirectional"))
    )
    (net (code "75") (name "/AddrRAM6") (class "Default")
      (node (ref "U4") (pin "T7") (pinfunction "IO,_DIFFIO_L53n_T7") (pintype "bidirectional"))
    )
    (net (code "76") (name "/AddrRAM7") (class "Default")
      (node (ref "U4") (pin "P7") (pinfunction "IO,_DIFFIO_L49n_P7") (pintype "bidirectional"))
    )
    (net (code "77") (name "/AddrRAM8") (class "Default")
      (node (ref "U4") (pin "P2") (pinfunction "IO,_DIFFIO_L32p,_(DQ1L)/(DQ3L)/(DQ1L)_P2") (pintype "bidirectional"))
    )
    (net (code "78") (name "/AddrRAM9") (class "Default")
      (node (ref "U4") (pin "R1") (pinfunction "IO,_DIFFIO_L33n,_(DQ1L)/(DQ3L)/(DQ1L)_R1") (pintype "bidirectional"))
    )
    (net (code "79") (name "/AddrRAM10") (class "Default")
      (node (ref "U4") (pin "R2") (pinfunction "IO,_DIFFIO_L33p,_(DQ1L)/(DQ3L)/(DQ1L)_R2") (pintype "bidirectional"))
    )
    (net (code "80") (name "/AddrRAM11") (class "Default")
      (node (ref "U4") (pin "V1") (pinfunction "IO,_DIFFIO_L38n,_(DQ3L)/(DQ3L)/(DQ1L)_V1") (pintype "bidirectional"))
    )
    (net (code "81") (name "/AddrRAM12") (class "Default")
      (node (ref "U4") (pin "U2") (pinfunction "IO,_DIFFIO_L35p,_(DM1L/BWS#1L)/(DM3L/BWS#3L)/(DM1L/BWS#1L)_U2") (pintype "bidirectional"))
    )
    (net (code "82") (name "/AddrRAM13") (class "Default")
      (node (ref "U4") (pin "V3") (pinfunction "IO,_RDN1_V3") (pintype "bidirectional"))
    )
    (net (code "83") (name "/AddrRAM14") (class "Default")
      (node (ref "U4") (pin "T4") (pinfunction "IO,_(DQS3L/CQ3L#,CDPCLK1)/(DQS3L/CQ3L#,CDPCLK1)/(DQS3L/CQ3L#,CDPCLK1)_T4") (pintype "bidirectional"))
    )
    (net (code "84") (name "/AddrRAM15") (class "Default")
      (node (ref "U4") (pin "R5") (pinfunction "IO,_VREFB2N3_R5") (pintype "bidirectional"))
    )
    (net (code "85") (name "/CE_RAM") (class "Default")
      (node (ref "U4") (pin "Y3") (pinfunction "IO,_DIFFIO_B4p,_(DQ3B)/(DQ3B)/(DQ5B)_Y3") (pintype "bidirectional"))
    )
    (net (code "86") (name "/C_C_LED") (class "Default")
      (node (ref "U4") (pin "N1") (pinfunction "IO,_DIFFIO_L29n,_(DQ1L)/(DQ3L)/(DQ1L)_N1") (pintype "bidirectional"))
    )
    (net (code "87") (name "/DEN") (class "Default")
      (node (ref "U4") (pin "B2") (pinfunction "IO,_DIFFIO_L2p,_(DQ2L)/(DQ1L)/(DQ1L)_B2") (pintype "bidirectional"))
    )
    (net (code "88") (name "/DataRAM0") (class "Default")
      (node (ref "U4") (pin "W6") (pinfunction "IO,_DIFFIO_B7p,_(DQ3B)/(DQ3B)/(DQ5B)_W6") (pintype "bidirectional"))
    )
    (net (code "89") (name "/DataRAM1") (class "Default")
      (node (ref "U4") (pin "U7") (pinfunction "IO,_DIFFIO_B3p_U7") (pintype "bidirectional"))
    )
    (net (code "90") (name "/DataRAM2") (class "Default")
      (node (ref "U4") (pin "V5") (pinfunction "IO,_DIFFIO_B1n,_(DM3B/BWS#3B)/(DM3B/BWS#3B)/(DM5B/BWS#5B)_V5") (pintype "bidirectional"))
    )
    (net (code "91") (name "/DataRAM3") (class "Default")
      (node (ref "U4") (pin "R6") (pinfunction "IO_R6") (pintype "bidirectional"))
    )
    (net (code "92") (name "/DataRAM4") (class "Default")
      (node (ref "U4") (pin "T5") (pinfunction "IO,_(DM3L/BWS#3L)/(DM3L/BWS#3L)/(DM1L/BWS#1L)_T5") (pintype "bidirectional"))
    )
    (net (code "93") (name "/DataRAM5") (class "Default")
      (node (ref "U4") (pin "Y4") (pinfunction "IO,_VREFB3N3_Y4") (pintype "bidirectional"))
    )
    (net (code "94") (name "/DataRAM6") (class "Default")
      (node (ref "U4") (pin "V4") (pinfunction "IO,_RUP1_V4") (pintype "bidirectional"))
    )
    (net (code "95") (name "/DataRAM7") (class "Default")
      (node (ref "U4") (pin "V2") (pinfunction "IO,_DIFFIO_L38p,_(DQ3L)/(DQ3L)/(DQ1L)_V2") (pintype "bidirectional"))
    )
    (net (code "96") (name "/DataRAM8") (class "Default")
      (node (ref "U4") (pin "T10") (pinfunction "IO,_DIFFIO_B15p_T10") (pintype "bidirectional"))
    )
    (net (code "97") (name "/DataRAM9") (class "Default")
      (node (ref "U4") (pin "P6") (pinfunction "IO,_DIFFIO_L52p_P6") (pintype "bidirectional"))
    )
    (net (code "98") (name "/DataRAM10") (class "Default")
      (node (ref "U4") (pin "P5") (pinfunction "IO,_VREFB2N1_P5") (pintype "bidirectional"))
    )
    (net (code "99") (name "/DataRAM11") (class "Default")
      (node (ref "U4") (pin "P4") (pinfunction "IO,_DIFFIO_L34p,_(DQS1L/CQ1L#,DPCLK1)/(DQS1L/CQ1L#,DPCLK1)/(DQS1L/CQ1L#,DPCLK1)_P4") (pintype "bidirectional"))
    )
    (net (code "100") (name "/DataRAM12") (class "Default")
      (node (ref "U4") (pin "P3") (pinfunction "IO,_DIFFIO_L34n,_(DQ1L)/(DQ3L)/(DQ1L)_P3") (pintype "bidirectional"))
    )
    (net (code "101") (name "/DataRAM13") (class "Default")
      (node (ref "U4") (pin "P1") (pinfunction "IO,_DIFFIO_L32n,_(DQ1L)/(DQ3L)/(DQ1L)_P1") (pintype "bidirectional"))
    )
    (net (code "102") (name "/DataRAM14") (class "Default")
      (node (ref "U4") (pin "T3") (pinfunction "IO,_VREFB2N2_T3") (pintype "bidirectional"))
    )
    (net (code "103") (name "/DataRAM15") (class "Default")
      (node (ref "U4") (pin "U1") (pinfunction "IO,_DIFFIO_L35n,_(DQ3L)/(DQ3L)/(DQ1L)_U1") (pintype "bidirectional"))
    )
    (net (code "104") (name "/ERR_LED") (class "Default")
      (node (ref "U4") (pin "M1") (pinfunction "IO,_DIFFIO_L27n,_(_)/(DQ1L)/(DQ1L)_M1") (pintype "bidirectional"))
    )
    (net (code "105") (name "/EthCOL") (class "Default")
      (node (ref "U4") (pin "AA7") (pinfunction "IO,_DIFFIO_B14p,_(DM5B/BWS#5B)/(DM3B/BWS#3B)/(DM5B/BWS#5B)_AA7") (pintype "bidirectional"))
    )
    (net (code "106") (name "/EthCRS") (class "Default")
      (node (ref "U4") (pin "AB7") (pinfunction "IO,_DIFFIO_B14n,_(DQ5B)/(DQ3B)/(DQ5B)_AB7") (pintype "bidirectional"))
    )
    (net (code "107") (name "/EthRXD0") (class "Default")
      (node (ref "U4") (pin "Y8") (pinfunction "IO,_(DQ5B)/(DQ3B)/(DQ5B)_Y8") (pintype "bidirectional"))
    )
    (net (code "108") (name "/EthRXD1") (class "Default")
      (node (ref "U4") (pin "W8") (pinfunction "IO,_(DQ3B)/(DQ3B)/(DQ5B)_W8") (pintype "bidirectional"))
    )
    (net (code "109") (name "/EthRXD2") (class "Default")
      (node (ref "U4") (pin "Y7") (pinfunction "IO,_DIFFIO_B12n,_(DQ3B)/(DQ3B)/(DQ5B)_Y7") (pintype "bidirectional"))
    )
    (net (code "110") (name "/EthRXD3") (class "Default")
      (node (ref "U4") (pin "W7") (pinfunction "IO,_DIFFIO_B12p,_(DQ3B)/(DQ3B)/(DQ5B)_W7") (pintype "bidirectional"))
    )
    (net (code "112") (name "/EthRX_CLK") (class "Default")
      (node (ref "U4") (pin "W10") (pinfunction "IO,_DIFFIO_B26p,_(DQ5B)/(DQ3B)/(DQ5B)_W10") (pintype "bidirectional"))
    )
    (net (code "113") (name "/EthRX_D V") (class "Default")
      (node (ref "U4") (pin "Y10") (pinfunction "IO,_DIFFIO_B26n,_(DQ5B)/(DQ3B)/(DQ5B)_Y10") (pintype "bidirectional"))
    )
    (net (code "114") (name "/EthTXD0") (class "Default")
      (node (ref "U4") (pin "AA9") (pinfunction "IO,_DIFFIO_B21p,_(DQ5B)/(DQ3B)/(DQ5B)_AA9") (pintype "bidirectional"))
    )
    (net (code "115") (name "/EthTXD1") (class "Default")
      (node (ref "U4") (pin "AB9") (pinfunction "IO,_DIFFIO_B21n,_(DQS5B/CQ5B#,DPCLK3)/(DQS5B/CQ5B#,DPCLK3)/(DQS5B/CQ5B#,DPCLK3)_AB9") (pintype "bidirectional"))
    )
    (net (code "116") (name "/EthTXD2") (class "Default")
      (node (ref "U4") (pin "AA8") (pinfunction "IO,_DIFFIO_B18p,_(DQ5B)/(DQ3B)/(DQ5B)_AA8") (pintype "bidirectional"))
    )
    (net (code "117") (name "/EthTXD3") (class "Default")
      (node (ref "U4") (pin "AB8") (pinfunction "IO,_DIFFIO_B18n,_(DQ5B)/(DQ3B)/(DQ5B)_AB8") (pintype "bidirectional"))
    )
    (net (code "118") (name "/EthTX_CLK") (class "Default")
      (node (ref "U4") (pin "AA10") (pinfunction "IO,_DIFFIO_B27p,_(DM4B)/(DM5B/BWS#5B)/(DM5B/BWS#5B)_AA10") (pintype "bidirectional"))
    )
    (net (code "119") (name "/EthTX_EN") (class "Default")
      (node (ref "U4") (pin "AB10") (pinfunction "IO,_DIFFIO_B27n,_(_)/(DQ5B)/(DQ5B)_AB10") (pintype "bidirectional"))
    )
    (net (code "120") (name "/Ext_reset") (class "Default")
      (node (ref "ExtReset1") (pin "1") (pinfunction "1_1") (pintype "passive"))
      (node (ref "U4") (pin "D2") (pinfunction "IO,_DIFFIO_L8p,_(DQ2L)/(DQ1L)/(DQ1L)_D2") (pintype "bidirectional"))
    )
    (net (code "121") (name "/FLData1") (class "Default")
      (node (ref "U4") (pin "A3") (pinfunction "IO,_DIFFIO_T4n,_(DATA10),_(DQ3T)/(DQ3T)/(DQ5T)_A3") (pintype "bidirectional"))
    )
    (net (code "122") (name "/FLData2") (class "Default")
      (node (ref "U4") (pin "B3") (pinfunction "IO,_DIFFIO_T4p,_(DATA11),_(DQ3T)/(DQ3T)/(DQ5T)_B3") (pintype "bidirectional"))
    )
    (net (code "123") (name "/FLData3") (class "Default")
      (node (ref "U4") (pin "A4") (pinfunction "IO,_DIFFIO_T6n,_(DQ3T)/(DQ3T)/(DQ5T)_A4") (pintype "bidirectional"))
    )
    (net (code "124") (name "/FLData4") (class "Default")
      (node (ref "U4") (pin "B4") (pinfunction "IO,_DIFFIO_T6p,_(DATA8),_(DQ3T)/(DQ3T)/(DQ5T)_B4") (pintype "bidirectional"))
    )
    (net (code "125") (name "/FLData5") (class "Default")
      (node (ref "U4") (pin "A5") (pinfunction "IO,_DIFFIO_T11p,_(DATA5),_(DQ3T)/(DQ3T)/(DQ5T)_A5") (pintype "bidirectional"))
    )
    (net (code "126") (name "/FLData6") (class "Default")
      (node (ref "U4") (pin "B5") (pinfunction "IO,_VREFB8N2_B5") (pintype "bidirectional"))
    )
    (net (code "127") (name "/FLData7") (class "Default")
      (node (ref "U4") (pin "A6") (pinfunction "IO,_DIFFIO_T18n,_(PADD19),_(DQ5T)/(DQ3T)/(DQ5T)_A6") (pintype "bidirectional"))
    )
    (net (code "128") (name "/FLData8") (class "Default")
      (node (ref "U4") (pin "B6") (pinfunction "IO,_DIFFIO_T18p,_(DATA15),_(DQ5T)/(DQ3T)/(DQ5T)_B6") (pintype "bidirectional"))
    )
    (net (code "129") (name "/FLData9") (class "Default")
      (node (ref "U4") (pin "A7") (pinfunction "IO,_DIFFIO_T19n,_(PADD18),_(DQ5T)/(DQ3T)/(DQ5T)_A7") (pintype "bidirectional"))
    )
    (net (code "130") (name "/FLData10") (class "Default")
      (node (ref "U4") (pin "B7") (pinfunction "IO,_DIFFIO_T19p,_(DATA4),_(DQ5T)/(DQ3T)/(DQ5T)_B7") (pintype "bidirectional"))
    )
    (net (code "131") (name "/FLData11") (class "Default")
      (node (ref "U4") (pin "A8") (pinfunction "IO,_DIFFIO_T20n,_(DATA2),_(DQ5T)/(DQ3T)/(DQ5T)_A8") (pintype "bidirectional"))
    )
    (net (code "132") (name "/FLData12") (class "Default")
      (node (ref "U4") (pin "B8") (pinfunction "IO,_DIFFIO_T20p,_(DATA3),_(DQ5T)/(DQ3T)/(DQ5T)_B8") (pintype "bidirectional"))
    )
    (net (code "133") (name "/FLData13") (class "Default")
      (node (ref "U4") (pin "A9") (pinfunction "IO,_DIFFIO_T24n,_(PADD16),_(DQ5T)/(DQ3T)/(DQ5T)_A9") (pintype "bidirectional"))
    )
    (net (code "134") (name "/FLData14") (class "Default")
      (node (ref "U4") (pin "B9") (pinfunction "IO,_DIFFIO_T24p,_(PADD17),_(DQS5T/CQ5T#,DPCLK10)/(DQS5T/CQ5T#,DPCLK10)/(DQS5T/CQ5T#,DPCLK10)_B9") (pintype "bidirectional"))
    )
    (net (code "136") (name "/Fquartz") (class "Default")
      (node (ref "U4") (pin "G17") (pinfunction "IO,_DIFFIO_R2p_G17") (pintype "bidirectional"))
    )
    (net (code "137") (name "/LB_RAM") (class "Default")
      (node (ref "U4") (pin "V10") (pinfunction "IO,_DIFFIO_B16p,_(DQS3B/CQ3B#,DPCLK2)/(DQS3B/CQ3B#,DPCLK2)/(DQS3B/CQ3B#,DPCLK2)_V10") (pintype "bidirectional"))
    )
    (net (code "138") (name "/LinkClk_N") (class "Default")
      (node (ref "U4") (pin "Y1") (pinfunction "IO,_DIFFIO_L45n,_(DQ3L)/(DQ3L)/(DQ1L)_Y1") (pintype "bidirectional"))
    )
    (net (code "139") (name "/LinkClk_P") (class "Default")
      (node (ref "U4") (pin "Y2") (pinfunction "IO,_DIFFIO_L45p,_(DQ3L)/(DQ3L)/(DQ1L)_Y2") (pintype "bidirectional"))
    )
    (net (code "140") (name "/NBit0") (class "Default")
      (node (ref "U4") (pin "A10") (pinfunction "IO,_DIFFIO_T25n,_(DQ5T)/(DQ3T)/(DQ5T)_A10") (pintype "bidirectional"))
    )
    (net (code "141") (name "/NBit1") (class "Default")
      (node (ref "U4") (pin "B10") (pinfunction "IO,_DIFFIO_T25p,_(PADD15)_B10") (pintype "bidirectional"))
    )
    (net (code "142") (name "/OE_RAM") (class "Default")
      (node (ref "U4") (pin "U10") (pinfunction "IO,_DIFFIO_B17n,_(DQ5B)/(DQ3B)/(DQ5B)_U10") (pintype "bidirectional"))
    )
    (net (code "143") (name "/Ok_LED") (class "Default")
      (node (ref "U4") (pin "N2") (pinfunction "IO,_DIFFIO_L29p,_(DQ1L)/(DQ3L)/(DQ1L)_N2") (pintype "bidirectional"))
    )
    (net (code "144") (name "/PLL_CLK") (class "Default")
      (node (ref "U4") (pin "G1") (pinfunction "CLK1,_DIFFCLK_0n_G1") (pintype "input"))
      (node (ref "U4") (pin "H1") (pinfunction "IO,_DIFFIO_L23n,_(DQ0L)/(DQ1L)/(DQ1L)_H1") (pintype "bidirectional"))
    )
    (net (code "149") (name "/REN") (class "Default")
      (node (ref "U4") (pin "C2") (pinfunction "IO,_DIFFIO_L7p,_(DQS2L/CQ3L,CDPCLK0)/(DQS2L/CQ3L,CDPCLK0)/(DQS2L/CQ3L,CDPCLK0)_C2") (pintype "bidirectional"))
    )
    (net (code "150") (name "/RPWDN") (class "Default")
      (node (ref "U4") (pin "C1") (pinfunction "IO,_DIFFIO_L7n,_(DQ2L)/(DQ1L)/(DQ1L)_C1") (pintype "bidirectional"))
    )
    (net (code "151") (name "/R_Sync") (class "Default")
      (node (ref "U4") (pin "C7") (pinfunction "IO,_DIFFIO_T16p,_(DATA13),_(DM5T/BWS#5T)/(DM3T/BWS#3T)/(DM5T/BWS#5T)_C7") (pintype "bidirectional"))
    )
    (net (code "152") (name "/Reset_ADC_1") (class "Default")
      (node (ref "U4") (pin "H17") (pinfunction "IO,_DIFFIO_R7p_H17") (pintype "bidirectional"))
    )
    (net (code "153") (name "/Reset_ADC_2") (class "Default")
      (node (ref "U4") (pin "H18") (pinfunction "IO,_VREFB6N1_H18") (pintype "bidirectional"))
    )
    (net (code "154") (name "/Reset_ADC_3") (class "Default")
      (node (ref "U4") (pin "G18") (pinfunction "IO,_DIFFIO_R7n,_(PADD23),_(DQ2R)/(DQ1R)/(DQ1R)_G18") (pintype "bidirectional"))
    )
    (net (code "155") (name "/SCLK") (class "Default")
      (node (ref "U4") (pin "W20") (pinfunction "IO,_(DQS3R/CQ3R#,CDPCLK4)/(DQS3R/CQ3R#,CDPCLK4)/(DQS3R/CQ3R#,CDPCLK4)_W20") (pintype "bidirectional"))
    )
    (net (code "156") (name "/SDATA_1") (class "Default")
      (node (ref "U4") (pin "U11") (pinfunction "IO,_VREFB3N0_U11") (pintype "bidirectional"))
    )
    (net (code "157") (name "/SDATA_2") (class "Default")
      (node (ref "U4") (pin "T17") (pinfunction "IO,_RUP3_T17") (pintype "bidirectional"))
    )
    (net (code "158") (name "/SDATA_3") (class "Default")
      (node (ref "U4") (pin "C19") (pinfunction "IO,_DIFFIO_T47n,_(DQ2T)/(DQ5T)/(DQ5T)_C19") (pintype "bidirectional"))
    )
    (net (code "159") (name "/SDOUT_1") (class "Default")
      (node (ref "U4") (pin "W15") (pinfunction "IO,_DIFFIO_B41n,_(DQ2B)/(DQ5B)/(DQ5B)_W15") (pintype "bidirectional"))
    )
    (net (code "160") (name "/SDOUT_2") (class "Default")
      (node (ref "U4") (pin "K18") (pinfunction "IO,_DIFFIO_R20p,_(DQ0R)/(DQ1R)/(DQ1R)_K18") (pintype "bidirectional"))
    )
    (net (code "161") (name "/SDOUT_3") (class "Default")
      (node (ref "U4") (pin "D15") (pinfunction "IO,_VREFB7N1_D15") (pintype "bidirectional"))
    )
    (net (code "162") (name "/SEN_1") (class "Default")
      (node (ref "U4") (pin "W14") (pinfunction "IO,_VREFB4N2_W14") (pintype "bidirectional"))
    )
    (net (code "163") (name "/SEN_2") (class "Default")
      (node (ref "U4") (pin "T18") (pinfunction "IO,_RDN3_T18") (pintype "bidirectional"))
    )
    (net (code "164") (name "/SEN_3") (class "Default")
      (node (ref "U4") (pin "D19") (pinfunction "IO,_DIFFIO_T47p,_(DQ2T)/(DQ5T)/(DQ5T)_D19") (pintype "bidirectional"))
    )
    (net (code "165") (name "/SLink_Data_N") (class "Default")
      (node (ref "U4") (pin "AB5") (pinfunction "IO,_DIFFIO_B8n_AB5") (pintype "bidirectional"))
    )
    (net (code "166") (name "/SLink_Data_P") (class "Default")
      (node (ref "U4") (pin "AA5") (pinfunction "IO,_DIFFIO_B8p,_(DQ3B)/(DQ3B)/(DQ5B)_AA5") (pintype "bidirectional"))
    )
    (net (code "167") (name "/SerClk") (class "Default")
      (node (ref "U4") (pin "B1") (pinfunction "IO,_DIFFIO_L2n,_(DQ2L)/(DQ1L)/(DQ1L)_B1") (pintype "bidirectional"))
    )
    (net (code "168") (name "/TCK") (class "Default")
      (node (ref "R52") (pin "2") (pinfunction "2_2") (pintype "passive"))
      (node (ref "U4") (pin "L2") (pinfunction "TCK_L2") (pintype "input"))
      (node (ref "U6") (pin "1") (pinfunction "1_1") (pintype "bidirectional"))
    )
    (net (code "169") (name "/TDI") (class "Default")
      (node (ref "R51") (pin "2") (pinfunction "2_2") (pintype "passive"))
      (node (ref "U4") (pin "L5") (pinfunction "TDI_L5") (pintype "input"))
      (node (ref "U6") (pin "9") (pinfunction "9_9") (pintype "bidirectional"))
    )
    (net (code "170") (name "/TDO") (class "Default")
      (node (ref "U4") (pin "L4") (pinfunction "TDO_L4") (pintype "output"))
      (node (ref "U6") (pin "3") (pinfunction "3_3") (pintype "bidirectional"))
    )
    (net (code "171") (name "/TMS") (class "Default")
      (node (ref "R53") (pin "2") (pinfunction "2_2") (pintype "passive"))
      (node (ref "U4") (pin "L1") (pinfunction "TMS_L1") (pintype "input"))
      (node (ref "U6") (pin "5") (pinfunction "5_5") (pintype "bidirectional"))
    )
    (net (code "172") (name "/TPWDN") (class "Default")
      (node (ref "U4") (pin "C8") (pinfunction "IO,_DIFFIO_T16n,_(DATA14),_(DQS3T/CQ3T#,DPCLK11)/(DQS3T/CQ3T#,DPCLK11)/(DQS3T/CQ3T#,DPCLK11)_C8") (pintype "bidirectional"))
    )
    (net (code "173") (name "/Test_pin1") (class "Default")
      (node (ref "U4") (pin "D7") (pinfunction "IO,_DIFFIO_T7p_D7") (pintype "bidirectional"))
    )
    (net (code "174") (name "/Test_pin2") (class "Default")
      (node (ref "U4") (pin "E7") (pinfunction "IO_E7") (pintype "bidirectional"))
    )
    (net (code "175") (name "/Test_pin3") (class "Default")
      (node (ref "U4") (pin "C6") (pinfunction "IO,_DIFFIO_T7n,_(DATA7),_(DQ3T)/(DQ3T)/(DQ5T)_C6") (pintype "bidirectional"))
    )
    (net (code "176") (name "/Test_pin4") (class "Default")
      (node (ref "U4") (pin "D6") (pinfunction "IO,_VREFB8N3_D6") (pintype "bidirectional"))
    )
    (net (code "177") (name "/Test_pin5") (class "Default")
      (node (ref "U4") (pin "C4") (pinfunction "IO,_DIFFIO_T3p,_(DATA12),_(DQS1T/CQ1T#,CDPCLK7)/(DQS1T/CQ1T#,CDPCLK7)/(DQS1T/CQ1T#,CDPCLK7)_C4") (pintype "bidirectional"))
    )
    (net (code "178") (name "/Test_pin6") (class "Default")
      (node (ref "U4") (pin "C3") (pinfunction "IO,_DIFFIO_T3n,_(DQ3T)/(DQ3T)/(DQ5T)_C3") (pintype "bidirectional"))
    )
    (net (code "179") (name "/Test_pin7") (class "Default")
      (node (ref "U4") (pin "E4") (pinfunction "IO,_DIFFIO_L4p,_(nRESET),_(DQ2L)/(DQ1L)/(DQ1L)_E4") (pintype "bidirectional"))
    )
    (net (code "180") (name "/Test_pin8") (class "Default")
      (node (ref "U4") (pin "E3") (pinfunction "IO,_DIFFIO_L4n,_(DQ2L)/(DQ1L)/(DQ1L)_E3") (pintype "bidirectional"))
    )
    (net (code "181") (name "/Test_pin9") (class "Default")
      (node (ref "U4") (pin "F2") (pinfunction "IO,_DIFFIO_L12p,_(DM2L)/(DM1L/BWS#1L)/(DM1L/BWS#1L)_F2") (pintype "bidirectional"))
    )
    (net (code "182") (name "/Test_pin10") (class "Default")
      (node (ref "U4") (pin "F1") (pinfunction "IO,_DIFFIO_L12n,_(DQ0L)/(DQ1L)/(DQ1L)_F1") (pintype "bidirectional"))
    )
    (net (code "183") (name "/UB_RAM") (class "Default")
      (node (ref "U4") (pin "T9") (pinfunction "IO,_DIFFIO_B11n_T9") (pintype "bidirectional"))
    )
    (net (code "184") (name "/WE_RAM") (class "Default")
      (node (ref "U4") (pin "AB3") (pinfunction "IO,_PLL1_CLKOUTn_AB3") (pintype "bidirectional"))
    )
    (net (code "185") (name "GND") (class "Default")
      (node (ref "C22") (pin "1") (pinfunction "1_1") (pintype "passive"))
      (node (ref "C23") (pin "1") (pinfunction "1_1") (pintype "passive"))
      (node (ref "C24") (pin "1") (pinfunction "1_1") (pintype "passive"))
      (node (ref "C25") (pin "1") (pinfunction "1_1") (pintype "passive"))
      (node (ref "C26") (pin "1") (pinfunction "1_1") (pintype "passive"))
      (node (ref "C27") (pin "1") (pinfunction "1_1") (pintype "passive"))
      (node (ref "C28") (pin "1") (pinfunction "1_1") (pintype "passive"))
      (node (ref "C29") (pin "1") (pinfunction "1_1") (pintype "passive"))
      (node (ref "C30") (pin "1") (pinfunction "1_1") (pintype "passive"))
      (node (ref "C31") (pin "1") (pinfunction "1_1") (pintype "passive"))
      (node (ref "C32") (pin "1") (pinfunction "1_1") (pintype "passive"))
      (node (ref "C33") (pin "1") (pinfunction "1_1") (pintype "passive"))
      (node (ref "C34") (pin "1") (pinfunction "1_1") (pintype "passive"))
      (node (ref "C35") (pin "1") (pinfunction "1_1") (pintype "passive"))
      (node (ref "C36") (pin "1") (pinfunction "1_1") (pintype "passive"))
      (node (ref "C37") (pin "1") (pinfunction "1_1") (pintype "passive"))
      (node (ref "C38") (pin "1") (pinfunction "1_1") (pintype "passive"))
      (node (ref "C39") (pin "1") (pinfunction "1_1") (pintype "passive"))
      (node (ref "C40") (pin "1") (pinfunction "1_1") (pintype "passive"))
      (node (ref "C41") (pin "1") (pinfunction "1_1") (pintype "passive"))
      (node (ref "C42") (pin "1") (pinfunction "1_1") (pintype "passive"))
      (node (ref "C43") (pin "1") (pinfunction "1_1") (pintype "passive"))
      (node (ref "C44") (pin "1") (pinfunction "1_1") (pintype "passive"))
      (node (ref "C45") (pin "1") (pinfunction "1_1") (pintype "passive"))
      (node (ref "C46") (pin "1") (pinfunction "1_1") (pintype "passive"))
      (node (ref "C47") (pin "1") (pinfunction "1_1") (pintype "passive"))
      (node (ref "C48") (pin "1") (pinfunction "1_1") (pintype "passive"))
      (node (ref "C49") (pin "1") (pinfunction "1_1") (pintype "passive"))
      (node (ref "C50") (pin "1") (pinfunction "1_1") (pintype "passive"))
      (node (ref "C51") (pin "1") (pinfunction "1_1") (pintype "passive"))
      (node (ref "C52") (pin "1") (pinfunction "1_1") (pintype "passive"))
      (node (ref "C53") (pin "1") (pinfunction "1_1") (pintype "passive"))
      (node (ref "C54") (pin "1") (pinfunction "1_1") (pintype "passive"))
      (node (ref "C55") (pin "1") (pinfunction "1_1") (pintype "passive"))
      (node (ref "C56") (pin "1") (pinfunction "1_1") (pintype "passive"))
      (node (ref "C57") (pin "1") (pinfunction "1_1") (pintype "passive"))
      (node (ref "C58") (pin "1") (pinfunction "1_1") (pintype "passive"))
      (node (ref "C59") (pin "1") (pinfunction "1_1") (pintype "passive"))
      (node (ref "C60") (pin "1") (pinfunction "1_1") (pintype "passive"))
      (node (ref "C61") (pin "1") (pinfunction "1_1") (pintype "passive"))
      (node (ref "C62") (pin "1") (pinfunction "1_1") (pintype "passive"))
      (node (ref "C63") (pin "1") (pinfunction "1_1") (pintype "passive"))
      (node (ref "C64") (pin "1") (pinfunction "1_1") (pintype "passive"))
      (node (ref "C65") (pin "1") (pinfunction "1_1") (pintype "passive"))
      (node (ref "C66") (pin "1") (pinfunction "1_1") (pintype "passive"))
      (node (ref "C67") (pin "1") (pinfunction "1_1") (pintype "passive"))
      (node (ref "ExtReset1") (pin "2") (pinfunction "2_2") (pintype "passive"))
      (node (ref "R50") (pin "1") (pinfunction "1_1") (pintype "passive"))
      (node (ref "R52") (pin "1") (pinfunction "1_1") (pintype "passive"))
      (node (ref "U4") (pin "A1") (pinfunction "GND_A1") (pintype "power_in"))
      (node (ref "U4") (pin "A11") (pinfunction "CLK10,_DIFFCLK_4n_A11") (pintype "input"))
      (node (ref "U4") (pin "A12") (pinfunction "CLK8,_DIFFCLK_5n_A12") (pintype "input"))
      (node (ref "U4") (pin "A22") (pinfunction "GND_A22") (pintype "power_in"))
      (node (ref "U4") (pin "AA11") (pinfunction "CLK15,_DIFFCLK_6p_AA11") (pintype "input"))
      (node (ref "U4") (pin "AA12") (pinfunction "CLK13,_DIFFCLK_7p_AA12") (pintype "input"))
      (node (ref "U4") (pin "AA2") (pinfunction "GND_AA2") (pintype "power_in"))
      (node (ref "U4") (pin "AA22") (pinfunction "GND_AA22") (pintype "power_in"))
      (node (ref "U4") (pin "AB1") (pinfunction "GND_AB1") (pintype "power_in"))
      (node (ref "U4") (pin "AB11") (pinfunction "CLK14,_DIFFCLK_6n_AB11") (pintype "input"))
      (node (ref "U4") (pin "AB12") (pinfunction "CLK12,_DIFFCLK_7n_AB12") (pintype "input"))
      (node (ref "U4") (pin "AB22") (pinfunction "GND_AB22") (pintype "power_in"))
      (node (ref "U4") (pin "AB6") (pinfunction "GND_AB6") (pintype "power_in"))
      (node (ref "U4") (pin "B11") (pinfunction "CLK11,_DIFFCLK_4p_B11") (pintype "input"))
      (node (ref "U4") (pin "B12") (pinfunction "CLK9,_DIFFCLK_5p_B12") (pintype "input"))
      (node (ref "U4") (pin "C11") (pinfunction "GND_C11") (pintype "power_in"))
      (node (ref "U4") (pin "C12") (pinfunction "GND_C12") (pintype "power_in"))
      (node (ref "U4") (pin "C14") (pinfunction "GND_C14") (pintype "power_in"))
      (node (ref "U4") (pin "C16") (pinfunction "GND_C16") (pintype "power_in"))
      (node (ref "U4") (pin "C18") (pinfunction "GND_C18") (pintype "power_in"))
      (node (ref "U4") (pin "C5") (pinfunction "GND_C5") (pintype "power_in"))
      (node (ref "U4") (pin "C9") (pinfunction "GND_C9") (pintype "power_in"))
      (node (ref "U4") (pin "D3") (pinfunction "GND_D3") (pintype "power_in"))
      (node (ref "U4") (pin "D8") (pinfunction "GND_D8") (pintype "power_in"))
      (node (ref "U4") (pin "E18") (pinfunction "GNDA2_E18") (pintype "power_in"))
      (node (ref "U4") (pin "E20") (pinfunction "GND_E20") (pintype "power_in"))
      (node (ref "U4") (pin "F12") (pinfunction "GND_F12") (pintype "power_in"))
      (node (ref "U4") (pin "F3") (pinfunction "GND_F3") (pintype "power_in"))
      (node (ref "U4") (pin "F5") (pinfunction "GNDA3_F5") (pintype "power_in"))
      (node (ref "U4") (pin "G2") (pinfunction "GND_G2") (pintype "power_in"))
      (node (ref "U4") (pin "G20") (pinfunction "GND_G20") (pintype "power_in"))
      (node (ref "U4") (pin "G21") (pinfunction "CLK4,_DIFFCLK_2p_G21") (pintype "input"))
      (node (ref "U4") (pin "G22") (pinfunction "CLK5,_DIFFCLK_2n_G22") (pintype "input"))
      (node (ref "U4") (pin "H12") (pinfunction "GND_H12") (pintype "power_in"))
      (node (ref "U4") (pin "H13") (pinfunction "GND_H13") (pintype "power_in"))
      (node (ref "U4") (pin "H3") (pinfunction "GND_H3") (pintype "power_in"))
      (node (ref "U4") (pin "J15") (pinfunction "GND_J15") (pintype "power_in"))
      (node (ref "U4") (pin "J19") (pinfunction "GND_J19") (pintype "power_in"))
      (node (ref "U4") (pin "J9") (pinfunction "GND_J9") (pintype "power_in"))
      (node (ref "U4") (pin "K10") (pinfunction "GND_K10") (pintype "power_in"))
      (node (ref "U4") (pin "K11") (pinfunction "GND_K11") (pintype "power_in"))
      (node (ref "U4") (pin "K12") (pinfunction "GND_K12") (pintype "power_in"))
      (node (ref "U4") (pin "K13") (pinfunction "GND_K13") (pintype "power_in"))
      (node (ref "U4") (pin "K16") (pinfunction "GND_K16") (pintype "power_in"))
      (node (ref "U4") (pin "K20") (pinfunction "MSEL3_K20") (pintype "input"))
      (node (ref "U4") (pin "K3") (pinfunction "GND_K3") (pintype "power_in"))
      (node (ref "U4") (pin "L10") (pinfunction "GND_L10") (pintype "power_in"))
      (node (ref "U4") (pin "L11") (pinfunction "GND_L11") (pintype "power_in"))
      (node (ref "U4") (pin "L12") (pinfunction "GND_L12") (pintype "power_in"))
      (node (ref "U4") (pin "L13") (pinfunction "GND_L13") (pintype "power_in"))
      (node (ref "U4") (pin "L15") (pinfunction "GND_L15") (pintype "power_in"))
      (node (ref "U4") (pin "L17") (pinfunction "MSEL2_L17") (pintype "input"))
      (node (ref "U4") (pin "L20") (pinfunction "GND_L20") (pintype "power_in"))
      (node (ref "U4") (pin "M10") (pinfunction "GND_M10") (pintype "power_in"))
      (node (ref "U4") (pin "M11") (pinfunction "GND_M11") (pintype "power_in"))
      (node (ref "U4") (pin "M12") (pinfunction "GND_M12") (pintype "power_in"))
      (node (ref "U4") (pin "M13") (pinfunction "GND_M13") (pintype "power_in"))
      (node (ref "U4") (pin "M17") (pinfunction "MSEL0_M17") (pintype "input"))
      (node (ref "U4") (pin "N10") (pinfunction "GND_N10") (pintype "power_in"))
      (node (ref "U4") (pin "N11") (pinfunction "GND_N11") (pintype "power_in"))
      (node (ref "U4") (pin "N12") (pinfunction "GND_N12") (pintype "power_in"))
      (node (ref "U4") (pin "N13") (pinfunction "GND_N13") (pintype "power_in"))
      (node (ref "U4") (pin "N15") (pinfunction "GND_N15") (pintype "power_in"))
      (node (ref "U4") (pin "N3") (pinfunction "GND_N3") (pintype "power_in"))
      (node (ref "U4") (pin "P19") (pinfunction "GND_P19") (pintype "power_in"))
      (node (ref "U4") (pin "P8") (pinfunction "GND_P8") (pintype "power_in"))
      (node (ref "U4") (pin "R11") (pinfunction "GND_R11") (pintype "power_in"))
      (node (ref "U4") (pin "R13") (pinfunction "GND_R13") (pintype "power_in"))
      (node (ref "U4") (pin "R3") (pinfunction "GND_R3") (pintype "power_in"))
      (node (ref "U4") (pin "R9") (pinfunction "GND_R9") (pintype "power_in"))
      (node (ref "U4") (pin "T1") (pinfunction "CLK3,_DIFFCLK_1n_T1") (pintype "input"))
      (node (ref "U4") (pin "T2") (pinfunction "CLK2,_DIFFCLK_1p_T2") (pintype "input"))
      (node (ref "U4") (pin "T20") (pinfunction "GND_T20") (pintype "power_in"))
      (node (ref "U4") (pin "T21") (pinfunction "CLK6,_DIFFCLK_3p_T21") (pintype "input"))
      (node (ref "U4") (pin "T22") (pinfunction "CLK7,_DIFFCLK_3n_T22") (pintype "input"))
      (node (ref "U4") (pin "U3") (pinfunction "GND_U3") (pintype "power_in"))
      (node (ref "U4") (pin "U5") (pinfunction "GNDA1_U5") (pintype "power_in"))
      (node (ref "U4") (pin "V18") (pinfunction "GNDA4_V18") (pintype "power_in"))
      (node (ref "U4") (pin "V20") (pinfunction "GND_V20") (pintype "power_in"))
      (node (ref "U4") (pin "W3") (pinfunction "GND_W3") (pintype "power_in"))
      (node (ref "U4") (pin "Y11") (pinfunction "GND_Y11") (pintype "power_in"))
      (node (ref "U4") (pin "Y12") (pinfunction "GND_Y12") (pintype "power_in"))
      (node (ref "U4") (pin "Y15") (pinfunction "GND_Y15") (pintype "power_in"))
      (node (ref "U4") (pin "Y16") (pinfunction "GND_Y16") (pintype "power_in"))
      (node (ref "U4") (pin "Y18") (pinfunction "GND_Y18") (pintype "power_in"))
      (node (ref "U4") (pin "Y20") (pinfunction "GND_Y20") (pintype "power_in"))
      (node (ref "U4") (pin "Y5") (pinfunction "GND_Y5") (pintype "power_in"))
      (node (ref "U4") (pin "Y9") (pinfunction "GND_Y9") (pintype "power_in"))
      (node (ref "U5") (pin "4") (pinfunction "GND_4") (pintype "power_in"))
      (node (ref "U6") (pin "10") (pinfunction "10_10") (pintype "bidirectional"))
      (node (ref "U6") (pin "2") (pinfunction "2_2") (pintype "bidirectional"))
    )
    (net (code "186") (name "Net-(U4J-CONF_DONE)") (class "Default")
      (node (ref "R47") (pin "2") (pinfunction "2_2") (pintype "passive"))
      (node (ref "U4") (pin "M18") (pinfunction "CONF_DONE_M18") (pintype "bidirectional"))
    )
    (net (code "187") (name "Net-(U4J-nCE)") (class "Default")
      (node (ref "R50") (pin "2") (pinfunction "2_2") (pintype "passive"))
      (node (ref "U4") (pin "L3") (pinfunction "nCE_L3") (pintype "input"))
    )
    (net (code "188") (name "Net-(U4J-nCONFIG)") (class "Default")
      (node (ref "R48") (pin "2") (pinfunction "2_2") (pintype "passive"))
      (node (ref "U4") (pin "K5") (pinfunction "nCONFIG_K5") (pintype "input"))
    )
    (net (code "189") (name "Net-(U4J-nSTATUS)") (class "Default")
      (node (ref "R49") (pin "2") (pinfunction "2_2") (pintype "passive"))
      (node (ref "U4") (pin "K6") (pinfunction "nSTATUS_K6") (pintype "bidirectional"))
    )
    (net (code "190") (name "unconnected-(U4A-IO,_(DQS0L{slash}CQ1L,DPCLK0){slash}(DQS0L{slash}CQ1L,DPCLK0){slash}(DQS0L{slash}CQ1L,DPCLK0)-PadJ4)") (class "Default")
      (node (ref "U4") (pin "J4") (pinfunction "IO,_(DQS0L/CQ1L,DPCLK0)/(DQS0L/CQ1L,DPCLK0)/(DQS0L/CQ1L,DPCLK0)_J4") (pintype "bidirectional"))
    )
    (net (code "191") (name "unconnected-(U4A-IO,_DIFFIO_L1n-PadG3)") (class "Default")
      (node (ref "U4") (pin "G3") (pinfunction "IO,_DIFFIO_L1n_G3") (pintype "bidirectional"))
    )
    (net (code "192") (name "unconnected-(U4A-IO,_DIFFIO_L1p-PadG4)") (class "Default")
      (node (ref "U4") (pin "G4") (pinfunction "IO,_DIFFIO_L1p_G4") (pintype "bidirectional"))
    )
    (net (code "193") (name "unconnected-(U4A-IO,_DIFFIO_L9n,_(DQ2L){slash}(DQ1L){slash}(DQ1L)-PadJ6)") (class "Default")
      (node (ref "U4") (pin "J6") (pinfunction "IO,_DIFFIO_L9n,_(DQ2L)/(DQ1L)/(DQ1L)_J6") (pintype "bidirectional"))
    )
    (net (code "194") (name "unconnected-(U4A-IO,_DIFFIO_L9p,_(DQ2L){slash}(DQ1L){slash}(DQ1L)-PadH6)") (class "Default")
      (node (ref "U4") (pin "H6") (pinfunction "IO,_DIFFIO_L9p,_(DQ2L)/(DQ1L)/(DQ1L)_H6") (pintype "bidirectional"))
    )
    (net (code "195") (name "unconnected-(U4A-IO,_DIFFIO_L10n,_(_){slash}(DQ1L){slash}(DQ1L)-PadE1)") (class "Default")
      (node (ref "U4") (pin "E1") (pinfunction "IO,_DIFFIO_L10n,_(_)/(DQ1L)/(DQ1L)_E1") (pintype "bidirectional"))
    )
    (net (code "196") (name "unconnected-(U4A-IO,_DIFFIO_L14n-PadJ8)") (class "Default")
      (node (ref "U4") (pin "J8") (pinfunction "IO,_DIFFIO_L14n_J8") (pintype "bidirectional"))
    )
    (net (code "197") (name "unconnected-(U4A-IO,_DIFFIO_L14p-PadH8)") (class "Default")
      (node (ref "U4") (pin "H8") (pinfunction "IO,_DIFFIO_L14p_H8") (pintype "bidirectional"))
    )
    (net (code "198") (name "unconnected-(U4A-IO,_DIFFIO_L18n-PadJ5)") (class "Default")
      (node (ref "U4") (pin "J5") (pinfunction "IO,_DIFFIO_L18n_J5") (pintype "bidirectional"))
    )
    (net (code "199") (name "unconnected-(U4A-IO,_DIFFIO_L20n-PadK8)") (class "Default")
      (node (ref "U4") (pin "K8") (pinfunction "IO,_DIFFIO_L20n_K8") (pintype "bidirectional"))
    )
    (net (code "200") (name "unconnected-(U4A-IO,_DIFFIO_L20p-PadL8)") (class "Default")
      (node (ref "U4") (pin "L8") (pinfunction "IO,_DIFFIO_L20p_L8") (pintype "bidirectional"))
    )
    (net (code "201") (name "unconnected-(U4A-IO,_DIFFIO_L21n-PadK7)") (class "Default")
      (node (ref "U4") (pin "K7") (pinfunction "IO,_DIFFIO_L21n_K7") (pintype "bidirectional"))
    )
    (net (code "202") (name "unconnected-(U4A-IO,_DIFFIO_L21p-PadJ7)") (class "Default")
      (node (ref "U4") (pin "J7") (pinfunction "IO,_DIFFIO_L21p_J7") (pintype "bidirectional"))
    )
    (net (code "203") (name "unconnected-(U4A-IO,_DIFFIO_L23p,_(DQ0L){slash}(DQ1L){slash}(DQ1L)-PadH2)") (class "Default")
      (node (ref "U4") (pin "H2") (pinfunction "IO,_DIFFIO_L23p,_(DQ0L)/(DQ1L)/(DQ1L)_H2") (pintype "bidirectional"))
    )
    (net (code "204") (name "unconnected-(U4A-IO,_DIFFIO_L24n,_(DQ0L){slash}(DQ1L){slash}(DQ1L)-PadJ1)") (class "Default")
      (node (ref "U4") (pin "J1") (pinfunction "IO,_DIFFIO_L24n,_(DQ0L)/(DQ1L)/(DQ1L)_J1") (pintype "bidirectional"))
    )
    (net (code "205") (name "unconnected-(U4A-IO,_DIFFIO_L24p,_(DQ0L){slash}(DQ1L){slash}(DQ1L)-PadJ2)") (class "Default")
      (node (ref "U4") (pin "J2") (pinfunction "IO,_DIFFIO_L24p,_(DQ0L)/(DQ1L)/(DQ1L)_J2") (pintype "bidirectional"))
    )
    (net (code "206") (name "unconnected-(U4A-IO,_VREFB1N0-PadG5)") (class "Default")
      (node (ref "U4") (pin "G5") (pinfunction "IO,_VREFB1N0_G5") (pintype "bidirectional"))
    )
    (net (code "207") (name "unconnected-(U4A-IO,_VREFB1N1-PadH7)") (class "Default")
      (node (ref "U4") (pin "H7") (pinfunction "IO,_VREFB1N1_H7") (pintype "bidirectional"))
    )
    (net (code "208") (name "unconnected-(U4A-IO,_VREFB1N2-PadH5)") (class "Default")
      (node (ref "U4") (pin "H5") (pinfunction "IO,_VREFB1N2_H5") (pintype "bidirectional"))
    )
    (net (code "209") (name "unconnected-(U4A-IO,_VREFB1N3-PadJ3)") (class "Default")
      (node (ref "U4") (pin "J3") (pinfunction "IO,_VREFB1N3_J3") (pintype "bidirectional"))
    )
    (net (code "210") (name "unconnected-(U4B-IO,_(DQ1L){slash}(DQ3L){slash}(DQ1L)-PadN5)") (class "Default")
      (node (ref "U4") (pin "N5") (pinfunction "IO,_(DQ1L)/(DQ3L)/(DQ1L)_N5") (pintype "bidirectional"))
    )
    (net (code "211") (name "unconnected-(U4B-IO,_DIFFIO_L26n,_(DQ0L){slash}(DQ1L){slash}(DQ1L)-PadM6)") (class "Default")
      (node (ref "U4") (pin "M6") (pinfunction "IO,_DIFFIO_L26n,_(DQ0L)/(DQ1L)/(DQ1L)_M6") (pintype "bidirectional"))
    )
    (net (code "212") (name "unconnected-(U4B-IO,_DIFFIO_L26p,_(DQ0L){slash}(DQ1L){slash}(DQ1L)-PadL6)") (class "Default")
      (node (ref "U4") (pin "L6") (pinfunction "IO,_DIFFIO_L26p,_(DQ0L)/(DQ1L)/(DQ1L)_L6") (pintype "bidirectional"))
    )
    (net (code "213") (name "unconnected-(U4B-IO,_DIFFIO_L27p,_(DQ0L){slash}(DQ1L){slash}(DQ1L)-PadM2)") (class "Default")
      (node (ref "U4") (pin "M2") (pinfunction "IO,_DIFFIO_L27p,_(DQ0L)/(DQ1L)/(DQ1L)_M2") (pintype "bidirectional"))
    )
    (net (code "214") (name "unconnected-(U4B-IO,_DIFFIO_L28n,_(DQ1L){slash}(DQ3L){slash}(DQ1L)-PadM3)") (class "Default")
      (node (ref "U4") (pin "M3") (pinfunction "IO,_DIFFIO_L28n,_(DQ1L)/(DQ3L)/(DQ1L)_M3") (pintype "bidirectional"))
    )
    (net (code "215") (name "unconnected-(U4B-IO,_DIFFIO_L28p,_(DM0L){slash}(DM1L{slash}BWS#1L){slash}(DM1L{slash}BWS#1L)-PadM4)") (class "Default")
      (node (ref "U4") (pin "M4") (pinfunction "IO,_DIFFIO_L28p,_(DM0L)/(DM1L/BWS#1L)/(DM1L/BWS#1L)_M4") (pintype "bidirectional"))
    )
    (net (code "216") (name "unconnected-(U4B-IO,_DIFFIO_L30n-PadL7)") (class "Default")
      (node (ref "U4") (pin "L7") (pinfunction "IO,_DIFFIO_L30n_L7") (pintype "bidirectional"))
    )
    (net (code "217") (name "unconnected-(U4B-IO,_DIFFIO_L41n-PadM7)") (class "Default")
      (node (ref "U4") (pin "M7") (pinfunction "IO,_DIFFIO_L41n_M7") (pintype "bidirectional"))
    )
    (net (code "218") (name "unconnected-(U4B-IO,_DIFFIO_L41p,_(DQ3L){slash}(DQ3L){slash}(DQ1L)-PadN6)") (class "Default")
      (node (ref "U4") (pin "N6") (pinfunction "IO,_DIFFIO_L41p,_(DQ3L)/(DQ3L)/(DQ1L)_N6") (pintype "bidirectional"))
    )
    (net (code "219") (name "unconnected-(U4B-IO,_DIFFIO_L42n-PadN8)") (class "Default")
      (node (ref "U4") (pin "N8") (pinfunction "IO,_DIFFIO_L42n_N8") (pintype "bidirectional"))
    )
    (net (code "220") (name "unconnected-(U4B-IO,_DIFFIO_L42p-PadM8)") (class "Default")
      (node (ref "U4") (pin "M8") (pinfunction "IO,_DIFFIO_L42p_M8") (pintype "bidirectional"))
    )
    (net (code "221") (name "unconnected-(U4B-IO,_DIFFIO_L44n,_(DQ3L){slash}(DQ3L){slash}(DQ1L)-PadW1)") (class "Default")
      (node (ref "U4") (pin "W1") (pinfunction "IO,_DIFFIO_L44n,_(DQ3L)/(DQ3L)/(DQ1L)_W1") (pintype "bidirectional"))
    )
    (net (code "222") (name "unconnected-(U4B-IO,_DIFFIO_L44p,_(DQ3L){slash}(DQ3L){slash}(DQ1L)-PadW2)") (class "Default")
      (node (ref "U4") (pin "W2") (pinfunction "IO,_DIFFIO_L44p,_(DQ3L)/(DQ3L)/(DQ1L)_W2") (pintype "bidirectional"))
    )
    (net (code "223") (name "unconnected-(U4B-IO,_DIFFIO_L49p-PadN7)") (class "Default")
      (node (ref "U4") (pin "N7") (pinfunction "IO,_DIFFIO_L49p_N7") (pintype "bidirectional"))
    )
    (net (code "224") (name "unconnected-(U4B-IO,_DIFFIO_L50n,_(DQ3L){slash}(DQ3L){slash}(DQ1L)-PadAA1)") (class "Default")
      (node (ref "U4") (pin "AA1") (pinfunction "IO,_DIFFIO_L50n,_(DQ3L)/(DQ3L)/(DQ1L)_AA1") (pintype "bidirectional"))
    )
    (net (code "225") (name "unconnected-(U4B-IO,_VREFB2N0-PadM5)") (class "Default")
      (node (ref "U4") (pin "M5") (pinfunction "IO,_VREFB2N0_M5") (pintype "bidirectional"))
    )
    (net (code "226") (name "unconnected-(U4C-IO,_(DQ3B){slash}(DQ3B){slash}(DQ5B)-PadAA4)") (class "Default")
      (node (ref "U4") (pin "AA4") (pinfunction "IO,_(DQ3B)/(DQ3B)/(DQ5B)_AA4") (pintype "bidirectional"))
    )
    (net (code "227") (name "unconnected-(U4C-IO,_DIFFIO_B1p-PadV6)") (class "Default")
      (node (ref "U4") (pin "V6") (pinfunction "IO,_DIFFIO_B1p_V6") (pintype "bidirectional"))
    )
    (net (code "228") (name "unconnected-(U4C-IO,_DIFFIO_B6p,_(DQS1B{slash}CQ1B#,CDPCLK2){slash}(DQS1B{slash}CQ1B#,CDPCLK2){slash}(DQS1B{slash}CQ1B#,CDPCLK2)-PadY6)") (class "Default")
      (node (ref "U4") (pin "Y6") (pinfunction "IO,_DIFFIO_B6p,_(DQS1B/CQ1B#,CDPCLK2)/(DQS1B/CQ1B#,CDPCLK2)/(DQS1B/CQ1B#,CDPCLK2)_Y6") (pintype "bidirectional"))
    )
    (net (code "229") (name "unconnected-(U4C-IO,_DIFFIO_B7n-PadV7)") (class "Default")
      (node (ref "U4") (pin "V7") (pinfunction "IO,_DIFFIO_B7n_V7") (pintype "bidirectional"))
    )
    (net (code "230") (name "unconnected-(U4C-IO,_DIFFIO_B15n-PadT11)") (class "Default")
      (node (ref "U4") (pin "T11") (pinfunction "IO,_DIFFIO_B15n_T11") (pintype "bidirectional"))
    )
    (net (code "231") (name "unconnected-(U4C-IO,_DIFFIO_B25n,_(DQ5B){slash}(DQ3B){slash}(DQ5B)-PadV11)") (class "Default")
      (node (ref "U4") (pin "V11") (pinfunction "IO,_DIFFIO_B25n,_(DQ5B)/(DQ3B)/(DQ5B)_V11") (pintype "bidirectional"))
    )
    (net (code "232") (name "unconnected-(U4C-IO,_PLL1_CLKOUTp-PadAA3)") (class "Default")
      (node (ref "U4") (pin "AA3") (pinfunction "IO,_PLL1_CLKOUTp_AA3") (pintype "bidirectional"))
    )
    (net (code "233") (name "unconnected-(U4C-IO,_VREFB3N2-PadAB4)") (class "Default")
      (node (ref "U4") (pin "AB4") (pinfunction "IO,_VREFB3N2_AB4") (pintype "bidirectional"))
    )
    (net (code "234") (name "unconnected-(U4D-IO,_(DQ2B){slash}(DQ5B){slash}(DQ5B)-PadAB18)") (class "Default")
      (node (ref "U4") (pin "AB18") (pinfunction "IO,_(DQ2B)/(DQ5B)/(DQ5B)_AB18") (pintype "bidirectional"))
    )
    (net (code "235") (name "unconnected-(U4D-IO,_(DQS2B{slash}CQ3B,DPCLK5){slash}(DQS2B{slash}CQ3B,DPCLK5){slash}(DQS2B{slash}CQ3B,DPCLK5)-PadV13)") (class "Default")
      (node (ref "U4") (pin "V13") (pinfunction "IO,_(DQS2B/CQ3B,DPCLK5)/(DQS2B/CQ3B,DPCLK5)/(DQS2B/CQ3B,DPCLK5)_V13") (pintype "bidirectional"))
    )
    (net (code "236") (name "unconnected-(U4D-IO,_DIFFIO_B32n,_(DQS4B{slash}CQ5B,DPCLK4){slash}(DQS4B{slash}CQ5B,DPCLK4){slash}(DQS4B{slash}CQ5B,DPCLK4)-PadY13)") (class "Default")
      (node (ref "U4") (pin "Y13") (pinfunction "IO,_DIFFIO_B32n,_(DQS4B/CQ5B,DPCLK4)/(DQS4B/CQ5B,DPCLK4)/(DQS4B/CQ5B,DPCLK4)_Y13") (pintype "bidirectional"))
    )
    (net (code "237") (name "unconnected-(U4D-IO,_DIFFIO_B32p,_(DQ4B){slash}(DQ5B){slash}(DQ5B)-PadW13)") (class "Default")
      (node (ref "U4") (pin "W13") (pinfunction "IO,_DIFFIO_B32p,_(DQ4B)/(DQ5B)/(DQ5B)_W13") (pintype "bidirectional"))
    )
    (net (code "238") (name "unconnected-(U4D-IO,_DIFFIO_B34p,_(DQ4B){slash}(DQ5B){slash}(DQ5B)-PadU12)") (class "Default")
      (node (ref "U4") (pin "U12") (pinfunction "IO,_DIFFIO_B34p,_(DQ4B)/(DQ5B)/(DQ5B)_U12") (pintype "bidirectional"))
    )
    (net (code "239") (name "unconnected-(U4D-IO,_DIFFIO_B36n-PadT13)") (class "Default")
      (node (ref "U4") (pin "T13") (pinfunction "IO,_DIFFIO_B36n_T13") (pintype "bidirectional"))
    )
    (net (code "240") (name "unconnected-(U4D-IO,_DIFFIO_B36p-PadT12)") (class "Default")
      (node (ref "U4") (pin "T12") (pinfunction "IO,_DIFFIO_B36p_T12") (pintype "bidirectional"))
    )
    (net (code "241") (name "unconnected-(U4D-IO,_DIFFIO_B38n-PadU13)") (class "Default")
      (node (ref "U4") (pin "U13") (pinfunction "IO,_DIFFIO_B38n_U13") (pintype "bidirectional"))
    )
    (net (code "242") (name "unconnected-(U4D-IO,_DIFFIO_B39n-PadU14)") (class "Default")
      (node (ref "U4") (pin "U14") (pinfunction "IO,_DIFFIO_B39n_U14") (pintype "bidirectional"))
    )
    (net (code "243") (name "unconnected-(U4D-IO,_DIFFIO_B39p,_(DQ2B){slash}(DQ5B){slash}(DQ5B)-PadV14)") (class "Default")
      (node (ref "U4") (pin "V14") (pinfunction "IO,_DIFFIO_B39p,_(DQ2B)/(DQ5B)/(DQ5B)_V14") (pintype "bidirectional"))
    )
    (net (code "244") (name "unconnected-(U4D-IO,_DIFFIO_B40n,_(DQ2B){slash}(DQ5B){slash}(DQ5B)-PadV15)") (class "Default")
      (node (ref "U4") (pin "V15") (pinfunction "IO,_DIFFIO_B40n,_(DQ2B)/(DQ5B)/(DQ5B)_V15") (pintype "bidirectional"))
    )
    (net (code "245") (name "unconnected-(U4D-IO,_DIFFIO_B40p-PadU15)") (class "Default")
      (node (ref "U4") (pin "U15") (pinfunction "IO,_DIFFIO_B40p_U15") (pintype "bidirectional"))
    )
    (net (code "246") (name "unconnected-(U4D-IO,_DIFFIO_B42n,_(DQ2B){slash}(DQ5B){slash}(DQ5B)-PadT15)") (class "Default")
      (node (ref "U4") (pin "T15") (pinfunction "IO,_DIFFIO_B42n,_(DQ2B)/(DQ5B)/(DQ5B)_T15") (pintype "bidirectional"))
    )
    (net (code "247") (name "unconnected-(U4D-IO,_DIFFIO_B42p-PadT14)") (class "Default")
      (node (ref "U4") (pin "T14") (pinfunction "IO,_DIFFIO_B42p_T14") (pintype "bidirectional"))
    )
    (net (code "248") (name "unconnected-(U4D-IO,_DIFFIO_B50n-PadU17)") (class "Default")
      (node (ref "U4") (pin "U17") (pinfunction "IO,_DIFFIO_B50n_U17") (pintype "bidirectional"))
    )
    (net (code "249") (name "unconnected-(U4D-IO,_DIFFIO_B50p-PadU16)") (class "Default")
      (node (ref "U4") (pin "U16") (pinfunction "IO,_DIFFIO_B50p_U16") (pintype "bidirectional"))
    )
    (net (code "250") (name "unconnected-(U4D-IO,_DIFFIO_B52n-PadR15)") (class "Default")
      (node (ref "U4") (pin "R15") (pinfunction "IO,_DIFFIO_B52n_R15") (pintype "bidirectional"))
    )
    (net (code "251") (name "unconnected-(U4D-IO,_DIFFIO_B52p-PadR14)") (class "Default")
      (node (ref "U4") (pin "R14") (pinfunction "IO,_DIFFIO_B52p_R14") (pintype "bidirectional"))
    )
    (net (code "252") (name "unconnected-(U4D-IO,_PLL4_CLKOUTn-PadR16)") (class "Default")
      (node (ref "U4") (pin "R16") (pinfunction "IO,_PLL4_CLKOUTn_R16") (pintype "bidirectional"))
    )
    (net (code "253") (name "unconnected-(U4D-IO,_PLL4_CLKOUTp-PadT16)") (class "Default")
      (node (ref "U4") (pin "T16") (pinfunction "IO,_PLL4_CLKOUTp_T16") (pintype "bidirectional"))
    )
    (net (code "254") (name "unconnected-(U4D-IO,_RDN2-PadAB19)") (class "Default")
      (node (ref "U4") (pin "AB19") (pinfunction "IO,_RDN2_AB19") (pintype "bidirectional"))
    )
    (net (code "255") (name "unconnected-(U4D-IO,_RUP2-PadAA19)") (class "Default")
      (node (ref "U4") (pin "AA19") (pinfunction "IO,_RUP2_AA19") (pintype "bidirectional"))
    )
    (net (code "256") (name "unconnected-(U4D-IO,_VREFB4N0-PadV16)") (class "Default")
      (node (ref "U4") (pin "V16") (pinfunction "IO,_VREFB4N0_V16") (pintype "bidirectional"))
    )
    (net (code "257") (name "unconnected-(U4D-IO,_VREFB4N1-PadAA18)") (class "Default")
      (node (ref "U4") (pin "AA18") (pinfunction "IO,_VREFB4N1_AA18") (pintype "bidirectional"))
    )
    (net (code "258") (name "unconnected-(U4D-IO,_VREFB4N3-PadV12)") (class "Default")
      (node (ref "U4") (pin "V12") (pinfunction "IO,_VREFB4N3_V12") (pintype "bidirectional"))
    )
    (net (code "259") (name "unconnected-(U4E-IO,_DIFFIO_R33n-PadN17)") (class "Default")
      (node (ref "U4") (pin "N17") (pinfunction "IO,_DIFFIO_R33n_N17") (pintype "bidirectional"))
    )
    (net (code "260") (name "unconnected-(U4E-IO,_DIFFIO_R33p,_(DQS1R{slash}CQ1R#,DPCLK6){slash}(DQS1R{slash}CQ1R#,DPCLK6){slash}(DQS1R{slash}CQ1R#,DPCLK6)-PadN18)") (class "Default")
      (node (ref "U4") (pin "N18") (pinfunction "IO,_DIFFIO_R33p,_(DQS1R/CQ1R#,DPCLK6)/(DQS1R/CQ1R#,DPCLK6)/(DQS1R/CQ1R#,DPCLK6)_N18") (pintype "bidirectional"))
    )
    (net (code "261") (name "unconnected-(U4E-IO,_DIFFIO_R36n,_(DQ1R){slash}(DQ3R){slash}(DQ1R)-PadN20)") (class "Default")
      (node (ref "U4") (pin "N20") (pinfunction "IO,_DIFFIO_R36n,_(DQ1R)/(DQ3R)/(DQ1R)_N20") (pintype "bidirectional"))
    )
    (net (code "262") (name "unconnected-(U4E-IO,_DIFFIO_R36p-PadN19)") (class "Default")
      (node (ref "U4") (pin "N19") (pinfunction "IO,_DIFFIO_R36p_N19") (pintype "bidirectional"))
    )
    (net (code "263") (name "unconnected-(U4E-IO,_DIFFIO_R40p-PadN16)") (class "Default")
      (node (ref "U4") (pin "N16") (pinfunction "IO,_DIFFIO_R40p_N16") (pintype "bidirectional"))
    )
    (net (code "264") (name "unconnected-(U4E-IO,_DIFFIO_R42n-PadR18)") (class "Default")
      (node (ref "U4") (pin "R18") (pinfunction "IO,_DIFFIO_R42n_R18") (pintype "bidirectional"))
    )
    (net (code "265") (name "unconnected-(U4E-IO,_DIFFIO_R42p,_(DM1R{slash}BWS#1R){slash}(DM3R{slash}BWS#3R){slash}(DM1R{slash}BWS#1R)-PadR19)") (class "Default")
      (node (ref "U4") (pin "R19") (pinfunction "IO,_DIFFIO_R42p,_(DM1R/BWS#1R)/(DM3R/BWS#3R)/(DM1R/BWS#1R)_R19") (pintype "bidirectional"))
    )
    (net (code "266") (name "unconnected-(U4E-IO,_DIFFIO_R44n,_(DQ3R){slash}(DQ3R){slash}(DQ1R)-PadR20)") (class "Default")
      (node (ref "U4") (pin "R20") (pinfunction "IO,_DIFFIO_R44n,_(DQ3R)/(DQ3R)/(DQ1R)_R20") (pintype "bidirectional"))
    )
    (net (code "267") (name "unconnected-(U4E-IO,_DIFFIO_R46n-PadP15)") (class "Default")
      (node (ref "U4") (pin "P15") (pinfunction "IO,_DIFFIO_R46n_P15") (pintype "bidirectional"))
    )
    (net (code "268") (name "unconnected-(U4E-IO,_DIFFIO_R46p-PadP16)") (class "Default")
      (node (ref "U4") (pin "P16") (pinfunction "IO,_DIFFIO_R46p_P16") (pintype "bidirectional"))
    )
    (net (code "269") (name "unconnected-(U4E-IO,_DIFFIO_R50n,_(DQ3R){slash}(DQ3R){slash}(DQ1R)-PadU20)") (class "Default")
      (node (ref "U4") (pin "U20") (pinfunction "IO,_DIFFIO_R50n,_(DQ3R)/(DQ3R)/(DQ1R)_U20") (pintype "bidirectional"))
    )
    (net (code "270") (name "unconnected-(U4E-IO,_DIFFIO_R50p-PadU19)") (class "Default")
      (node (ref "U4") (pin "U19") (pinfunction "IO,_DIFFIO_R50p_U19") (pintype "bidirectional"))
    )
    (net (code "271") (name "unconnected-(U4E-IO,_DIFFIO_R56p,_(DM3R{slash}BWS#3R){slash}(DM3R{slash}BWS#3R){slash}(DM1R{slash}BWS#1R)-PadAA21)") (class "Default")
      (node (ref "U4") (pin "AA21") (pinfunction "IO,_DIFFIO_R56p,_(DM3R/BWS#3R)/(DM3R/BWS#3R)/(DM1R/BWS#1R)_AA21") (pintype "bidirectional"))
    )
    (net (code "272") (name "unconnected-(U4E-IO,_VREFB5N0-PadM16)") (class "Default")
      (node (ref "U4") (pin "M16") (pinfunction "IO,_VREFB5N0_M16") (pintype "bidirectional"))
    )
    (net (code "273") (name "unconnected-(U4E-IO,_VREFB5N1-PadP20)") (class "Default")
      (node (ref "U4") (pin "P20") (pinfunction "IO,_VREFB5N1_P20") (pintype "bidirectional"))
    )
    (net (code "274") (name "unconnected-(U4E-IO,_VREFB5N2-PadR17)") (class "Default")
      (node (ref "U4") (pin "R17") (pinfunction "IO,_VREFB5N2_R17") (pintype "bidirectional"))
    )
    (net (code "275") (name "unconnected-(U4E-IO,_VREFB5N3-PadW19)") (class "Default")
      (node (ref "U4") (pin "W19") (pinfunction "IO,_VREFB5N3_W19") (pintype "bidirectional"))
    )
    (net (code "276") (name "unconnected-(U4E-IO-PadP17)") (class "Default")
      (node (ref "U4") (pin "P17") (pinfunction "IO_P17") (pintype "bidirectional"))
    )
    (net (code "277") (name "unconnected-(U4F-IO,_DIFFIO_R4n,_(PADD20),_(DQS2R{slash}CQ3R,CDPCLK5){slash}(DQS2R{slash}CQ3R,CDPCLK5){slash}(DQS2R{slash}CQ3R,CDPCLK5)-PadC20)") (class "Default")
      (node (ref "U4") (pin "C20") (pinfunction "IO,_DIFFIO_R4n,_(PADD20),_(DQS2R/CQ3R,CDPCLK5)/(DQS2R/CQ3R,CDPCLK5)/(DQS2R/CQ3R,CDPCLK5)_C20") (pintype "bidirectional"))
    )
    (net (code "278") (name "unconnected-(U4F-IO,_DIFFIO_R8n,_(nAVD),_(DQ2R){slash}(DQ1R){slash}(DQ1R)-PadF20)") (class "Default")
      (node (ref "U4") (pin "F20") (pinfunction "IO,_DIFFIO_R8n,_(nAVD),_(DQ2R)/(DQ1R)/(DQ1R)_F20") (pintype "bidirectional"))
    )
    (net (code "279") (name "unconnected-(U4F-IO,_DIFFIO_R8p,_(DQ2R){slash}(DQ1R){slash}(DQ1R)-PadF19)") (class "Default")
      (node (ref "U4") (pin "F19") (pinfunction "IO,_DIFFIO_R8p,_(DQ2R)/(DQ1R)/(DQ1R)_F19") (pintype "bidirectional"))
    )
    (net (code "280") (name "unconnected-(U4F-IO,_DIFFIO_R10n-PadJ17)") (class "Default")
      (node (ref "U4") (pin "J17") (pinfunction "IO,_DIFFIO_R10n_J17") (pintype "bidirectional"))
    )
    (net (code "281") (name "unconnected-(U4F-IO,_DIFFIO_R10p-PadH16)") (class "Default")
      (node (ref "U4") (pin "H16") (pinfunction "IO,_DIFFIO_R10p_H16") (pintype "bidirectional"))
    )
    (net (code "282") (name "unconnected-(U4F-IO,_DIFFIO_R13n,_(DQ0R){slash}(DQ1R){slash}(DQ1R)-PadH20)") (class "Default")
      (node (ref "U4") (pin "H20") (pinfunction "IO,_DIFFIO_R13n,_(DQ0R)/(DQ1R)/(DQ1R)_H20") (pintype "bidirectional"))
    )
    (net (code "283") (name "unconnected-(U4F-IO,_DIFFIO_R13p,_(DQ0R){slash}(DQ1R){slash}(DQ1R)-PadH19)") (class "Default")
      (node (ref "U4") (pin "H19") (pinfunction "IO,_DIFFIO_R13p,_(DQ0R)/(DQ1R)/(DQ1R)_H19") (pintype "bidirectional"))
    )
    (net (code "284") (name "unconnected-(U4F-IO,_DIFFIO_R20n-PadK17)") (class "Default")
      (node (ref "U4") (pin "K17") (pinfunction "IO,_DIFFIO_R20n_K17") (pintype "bidirectional"))
    )
    (net (code "285") (name "unconnected-(U4F-IO,_DIFFIO_R24n,_(nCEO)-PadK22)") (class "Default")
      (node (ref "U4") (pin "K22") (pinfunction "IO,_DIFFIO_R24n,_(nCEO)_K22") (pintype "bidirectional"))
    )
    (net (code "286") (name "unconnected-(U4F-IO,_DIFFIO_R24p,_(CLKUSR)-PadK21)") (class "Default")
      (node (ref "U4") (pin "K21") (pinfunction "IO,_DIFFIO_R24p,_(CLKUSR)_K21") (pintype "bidirectional"))
    )
    (net (code "287") (name "unconnected-(U4F-IO,_DIFFIO_R27n,_(INIT_DONE)-PadL22)") (class "Default")
      (node (ref "U4") (pin "L22") (pinfunction "IO,_DIFFIO_R27n,_(INIT_DONE)_L22") (pintype "bidirectional"))
    )
    (net (code "288") (name "unconnected-(U4F-IO,_DIFFIO_R27p,_(CRC_ERROR)-PadL21)") (class "Default")
      (node (ref "U4") (pin "L21") (pinfunction "IO,_DIFFIO_R27p,_(CRC_ERROR)_L21") (pintype "bidirectional"))
    )
    (net (code "289") (name "unconnected-(U4F-IO,_VREFB6N0-PadD20)") (class "Default")
      (node (ref "U4") (pin "D20") (pinfunction "IO,_VREFB6N0_D20") (pintype "bidirectional"))
    )
    (net (code "290") (name "unconnected-(U4F-IO,_VREFB6N2-PadJ18)") (class "Default")
      (node (ref "U4") (pin "J18") (pinfunction "IO,_VREFB6N2_J18") (pintype "bidirectional"))
    )
    (net (code "291") (name "unconnected-(U4F-IO,_VREFB6N3-PadK19)") (class "Default")
      (node (ref "U4") (pin "K19") (pinfunction "IO,_VREFB6N3_K19") (pintype "bidirectional"))
    )
    (net (code "292") (name "unconnected-(U4G-IO,_DIFFIO_T27n,_(PADD13)-PadE11)") (class "Default")
      (node (ref "U4") (pin "E11") (pinfunction "IO,_DIFFIO_T27n,_(PADD13)_E11") (pintype "bidirectional"))
    )
    (net (code "293") (name "unconnected-(U4G-IO,_DIFFIO_T27p,_(PADD14),_(DM4T){slash}(DM5T{slash}BWS#5T){slash}(DM5T{slash}BWS#5T)-PadF11)") (class "Default")
      (node (ref "U4") (pin "F11") (pinfunction "IO,_DIFFIO_T27p,_(PADD14),_(DM4T)/(DM5T/BWS#5T)/(DM5T/BWS#5T)_F11") (pintype "bidirectional"))
    )
    (net (code "294") (name "unconnected-(U4G-IO,_DIFFIO_T28p,_(_){slash}(DQ5T){slash}(DQ5T)-PadE12)") (class "Default")
      (node (ref "U4") (pin "E12") (pinfunction "IO,_DIFFIO_T28p,_(_)/(DQ5T)/(DQ5T)_E12") (pintype "bidirectional"))
    )
    (net (code "295") (name "unconnected-(U4G-IO,_DIFFIO_T37p,_(PADD4),_(DQS2T{slash}CQ3T,DPCLK8){slash}(DQS2T{slash}CQ3T,DPCLK8){slash}(DQS2T{slash}CQ3T,DPCLK8)-PadF13)") (class "Default")
      (node (ref "U4") (pin "F13") (pinfunction "IO,_DIFFIO_T37p,_(PADD4),_(DQS2T/CQ3T,DPCLK8)/(DQS2T/CQ3T,DPCLK8)/(DQS2T/CQ3T,DPCLK8)_F13") (pintype "bidirectional"))
    )
    (net (code "296") (name "unconnected-(U4G-IO,_DIFFIO_T38n,_(PADD3),_(DQ4T){slash}(DQ5T){slash}(DQ5T)-PadE14)") (class "Default")
      (node (ref "U4") (pin "E14") (pinfunction "IO,_DIFFIO_T38n,_(PADD3),_(DQ4T)/(DQ5T)/(DQ5T)_E14") (pintype "bidirectional"))
    )
    (net (code "297") (name "unconnected-(U4G-IO,_DIFFIO_T42n-PadG13)") (class "Default")
      (node (ref "U4") (pin "G13") (pinfunction "IO,_DIFFIO_T42n_G13") (pintype "bidirectional"))
    )
    (net (code "298") (name "unconnected-(U4G-IO,_DIFFIO_T44n,_(DQ2T){slash}(DQ5T){slash}(DQ5T)-PadE15)") (class "Default")
      (node (ref "U4") (pin "E15") (pinfunction "IO,_DIFFIO_T44n,_(DQ2T)/(DQ5T)/(DQ5T)_E15") (pintype "bidirectional"))
    )
    (net (code "299") (name "unconnected-(U4G-IO,_DIFFIO_T44p-PadG14)") (class "Default")
      (node (ref "U4") (pin "G14") (pinfunction "IO,_DIFFIO_T44p_G14") (pintype "bidirectional"))
    )
    (net (code "300") (name "unconnected-(U4G-IO,_DIFFIO_T46p,_(DQ2T){slash}(DQ5T){slash}(DQ5T)-PadC17)") (class "Default")
      (node (ref "U4") (pin "C17") (pinfunction "IO,_DIFFIO_T46p,_(DQ2T)/(DQ5T)/(DQ5T)_C17") (pintype "bidirectional"))
    )
    (net (code "301") (name "unconnected-(U4G-IO,_DIFFIO_T48n-PadH15)") (class "Default")
      (node (ref "U4") (pin "H15") (pinfunction "IO,_DIFFIO_T48n_H15") (pintype "bidirectional"))
    )
    (net (code "302") (name "unconnected-(U4G-IO,_DIFFIO_T48p-PadH14)") (class "Default")
      (node (ref "U4") (pin "H14") (pinfunction "IO,_DIFFIO_T48p_H14") (pintype "bidirectional"))
    )
    (net (code "303") (name "unconnected-(U4G-IO,_DIFFIO_T49n-PadG15)") (class "Default")
      (node (ref "U4") (pin "G15") (pinfunction "IO,_DIFFIO_T49n_G15") (pintype "bidirectional"))
    )
    (net (code "304") (name "unconnected-(U4G-IO,_DIFFIO_T49p,_(DQS0T{slash}CQ1T,CDPCLK6){slash}(DQS0T{slash}CQ1T,CDPCLK6){slash}(DQS0T{slash}CQ1T,CDPCLK6)-PadF14)") (class "Default")
      (node (ref "U4") (pin "F14") (pinfunction "IO,_DIFFIO_T49p,_(DQS0T/CQ1T,CDPCLK6)/(DQS0T/CQ1T,CDPCLK6)/(DQS0T/CQ1T,CDPCLK6)_F14") (pintype "bidirectional"))
    )
    (net (code "305") (name "unconnected-(U4G-IO,_DIFFIO_T50n,_(DQ2T){slash}(DQ5T){slash}(DQ5T)-PadF15)") (class "Default")
      (node (ref "U4") (pin "F15") (pinfunction "IO,_DIFFIO_T50n,_(DQ2T)/(DQ5T)/(DQ5T)_F15") (pintype "bidirectional"))
    )
    (net (code "306") (name "unconnected-(U4G-IO,_DIFFIO_T50p-PadG16)") (class "Default")
      (node (ref "U4") (pin "G16") (pinfunction "IO,_DIFFIO_T50p_G16") (pintype "bidirectional"))
    )
    (net (code "307") (name "unconnected-(U4G-IO,_DIFFIO_T51n-PadF16)") (class "Default")
      (node (ref "U4") (pin "F16") (pinfunction "IO,_DIFFIO_T51n_F16") (pintype "bidirectional"))
    )
    (net (code "308") (name "unconnected-(U4G-IO,_DIFFIO_T51p,_(DQ2T){slash}(DQ5T){slash}(DQ5T)-PadE16)") (class "Default")
      (node (ref "U4") (pin "E16") (pinfunction "IO,_DIFFIO_T51p,_(DQ2T)/(DQ5T)/(DQ5T)_E16") (pintype "bidirectional"))
    )
    (net (code "309") (name "unconnected-(U4G-IO,_PLL2_CLKOUTn-PadA20)") (class "Default")
      (node (ref "U4") (pin "A20") (pinfunction "IO,_PLL2_CLKOUTn_A20") (pintype "bidirectional"))
    )
    (net (code "310") (name "unconnected-(U4G-IO,_PLL2_CLKOUTp-PadB20)") (class "Default")
      (node (ref "U4") (pin "B20") (pinfunction "IO,_PLL2_CLKOUTp_B20") (pintype "bidirectional"))
    )
    (net (code "311") (name "unconnected-(U4G-IO,_RDN4-PadA19)") (class "Default")
      (node (ref "U4") (pin "A19") (pinfunction "IO,_RDN4_A19") (pintype "bidirectional"))
    )
    (net (code "312") (name "unconnected-(U4G-IO,_RUP4-PadB19)") (class "Default")
      (node (ref "U4") (pin "B19") (pinfunction "IO,_RUP4_B19") (pintype "bidirectional"))
    )
    (net (code "313") (name "unconnected-(U4G-IO,_VREFB7N0-PadD17)") (class "Default")
      (node (ref "U4") (pin "D17") (pinfunction "IO,_VREFB7N0_D17") (pintype "bidirectional"))
    )
    (net (code "314") (name "unconnected-(U4G-IO,_VREFB7N2-PadC15)") (class "Default")
      (node (ref "U4") (pin "C15") (pinfunction "IO,_VREFB7N2_C15") (pintype "bidirectional"))
    )
    (net (code "315") (name "unconnected-(U4G-IO,_VREFB7N3-PadE13)") (class "Default")
      (node (ref "U4") (pin "E13") (pinfunction "IO,_VREFB7N3_E13") (pintype "bidirectional"))
    )
    (net (code "316") (name "unconnected-(U4H-IO,_DIFFIO_T1n,_(DM3T{slash}BWS#3T){slash}(DM3T{slash}BWS#3T){slash}(DM5T{slash}BWS#5T)-PadF7)") (class "Default")
      (node (ref "U4") (pin "F7") (pinfunction "IO,_DIFFIO_T1n,_(DM3T/BWS#3T)/(DM3T/BWS#3T)/(DM5T/BWS#5T)_F7") (pintype "bidirectional"))
    )
    (net (code "317") (name "unconnected-(U4H-IO,_DIFFIO_T1p-PadG7)") (class "Default")
      (node (ref "U4") (pin "G7") (pinfunction "IO,_DIFFIO_T1p_G7") (pintype "bidirectional"))
    )
    (net (code "318") (name "unconnected-(U4H-IO,_DIFFIO_T5n,_(DATA9),_(DQ3T){slash}(DQ3T){slash}(DQ5T)-PadF8)") (class "Default")
      (node (ref "U4") (pin "F8") (pinfunction "IO,_DIFFIO_T5n,_(DATA9),_(DQ3T)/(DQ3T)/(DQ5T)_F8") (pintype "bidirectional"))
    )
    (net (code "319") (name "unconnected-(U4H-IO,_DIFFIO_T5p-PadG8)") (class "Default")
      (node (ref "U4") (pin "G8") (pinfunction "IO,_DIFFIO_T5p_G8") (pintype "bidirectional"))
    )
    (net (code "320") (name "unconnected-(U4H-IO,_DIFFIO_T8n-PadG10)") (class "Default")
      (node (ref "U4") (pin "G10") (pinfunction "IO,_DIFFIO_T8n_G10") (pintype "bidirectional"))
    )
    (net (code "321") (name "unconnected-(U4H-IO,_DIFFIO_T8p,_(DATA6),_(DQ3T){slash}(DQ3T){slash}(DQ5T)-PadF10)") (class "Default")
      (node (ref "U4") (pin "F10") (pinfunction "IO,_DIFFIO_T8p,_(DATA6),_(DQ3T)/(DQ3T)/(DQ5T)_F10") (pintype "bidirectional"))
    )
    (net (code "322") (name "unconnected-(U4H-IO,_DIFFIO_T14n-PadH11)") (class "Default")
      (node (ref "U4") (pin "H11") (pinfunction "IO,_DIFFIO_T14n_H11") (pintype "bidirectional"))
    )
    (net (code "323") (name "unconnected-(U4H-IO,_DIFFIO_T14p-PadH10)") (class "Default")
      (node (ref "U4") (pin "H10") (pinfunction "IO,_DIFFIO_T14p_H10") (pintype "bidirectional"))
    )
    (net (code "324") (name "unconnected-(U4H-IO,_DIFFIO_T22n-PadG11)") (class "Default")
      (node (ref "U4") (pin "G11") (pinfunction "IO,_DIFFIO_T22n_G11") (pintype "bidirectional"))
    )
    (net (code "325") (name "unconnected-(U4H-IO,_DIFFIO_T26n,_(DQ5T){slash}(DQ3T){slash}(DQ5T)-PadD10)") (class "Default")
      (node (ref "U4") (pin "D10") (pinfunction "IO,_DIFFIO_T26n,_(DQ5T)/(DQ3T)/(DQ5T)_D10") (pintype "bidirectional"))
    )
    (net (code "326") (name "unconnected-(U4H-IO,_DIFFIO_T26p-PadE10)") (class "Default")
      (node (ref "U4") (pin "E10") (pinfunction "IO,_DIFFIO_T26p_E10") (pintype "bidirectional"))
    )
    (net (code "327") (name "unconnected-(U4H-IO,_PLL3_CLKOUTn-PadE6)") (class "Default")
      (node (ref "U4") (pin "E6") (pinfunction "IO,_PLL3_CLKOUTn_E6") (pintype "bidirectional"))
    )
    (net (code "328") (name "unconnected-(U4H-IO,_PLL3_CLKOUTp-PadE5)") (class "Default")
      (node (ref "U4") (pin "E5") (pinfunction "IO,_PLL3_CLKOUTp_E5") (pintype "bidirectional"))
    )
    (net (code "329") (name "unconnected-(U4H-IO,_VREFB8N0-PadC10)") (class "Default")
      (node (ref "U4") (pin "C10") (pinfunction "IO,_VREFB8N0_C10") (pintype "bidirectional"))
    )
    (net (code "330") (name "unconnected-(U4H-IO,_VREFB8N1-PadE9)") (class "Default")
      (node (ref "U4") (pin "E9") (pinfunction "IO,_VREFB8N1_E9") (pintype "bidirectional"))
    )
    (net (code "331") (name "unconnected-(U4H-IO-PadF9)") (class "Default")
      (node (ref "U4") (pin "F9") (pinfunction "IO_F9") (pintype "bidirectional"))
    )
    (net (code "332") (name "unconnected-(U4H-IO-PadG9)") (class "Default")
      (node (ref "U4") (pin "G9") (pinfunction "IO_G9") (pintype "bidirectional"))
    )
    (net (code "333") (name "unconnected-(U6-Pad6)") (class "Default")
      (node (ref "U6") (pin "6") (pinfunction "6_6") (pintype "bidirectional"))
    )
    (net (code "334") (name "unconnected-(U6-Pad7)") (class "Default")
      (node (ref "U6") (pin "7") (pinfunction "7_7") (pintype "bidirectional"))
    )
    (net (code "335") (name "unconnected-(U6-Pad8)") (class "Default")
      (node (ref "U6") (pin "8") (pinfunction "8_8") (pintype "bidirectional"))
    )
  )
)
